# Hauptplatine.net
KiCad netlist of a schematic drawn in EAGLE
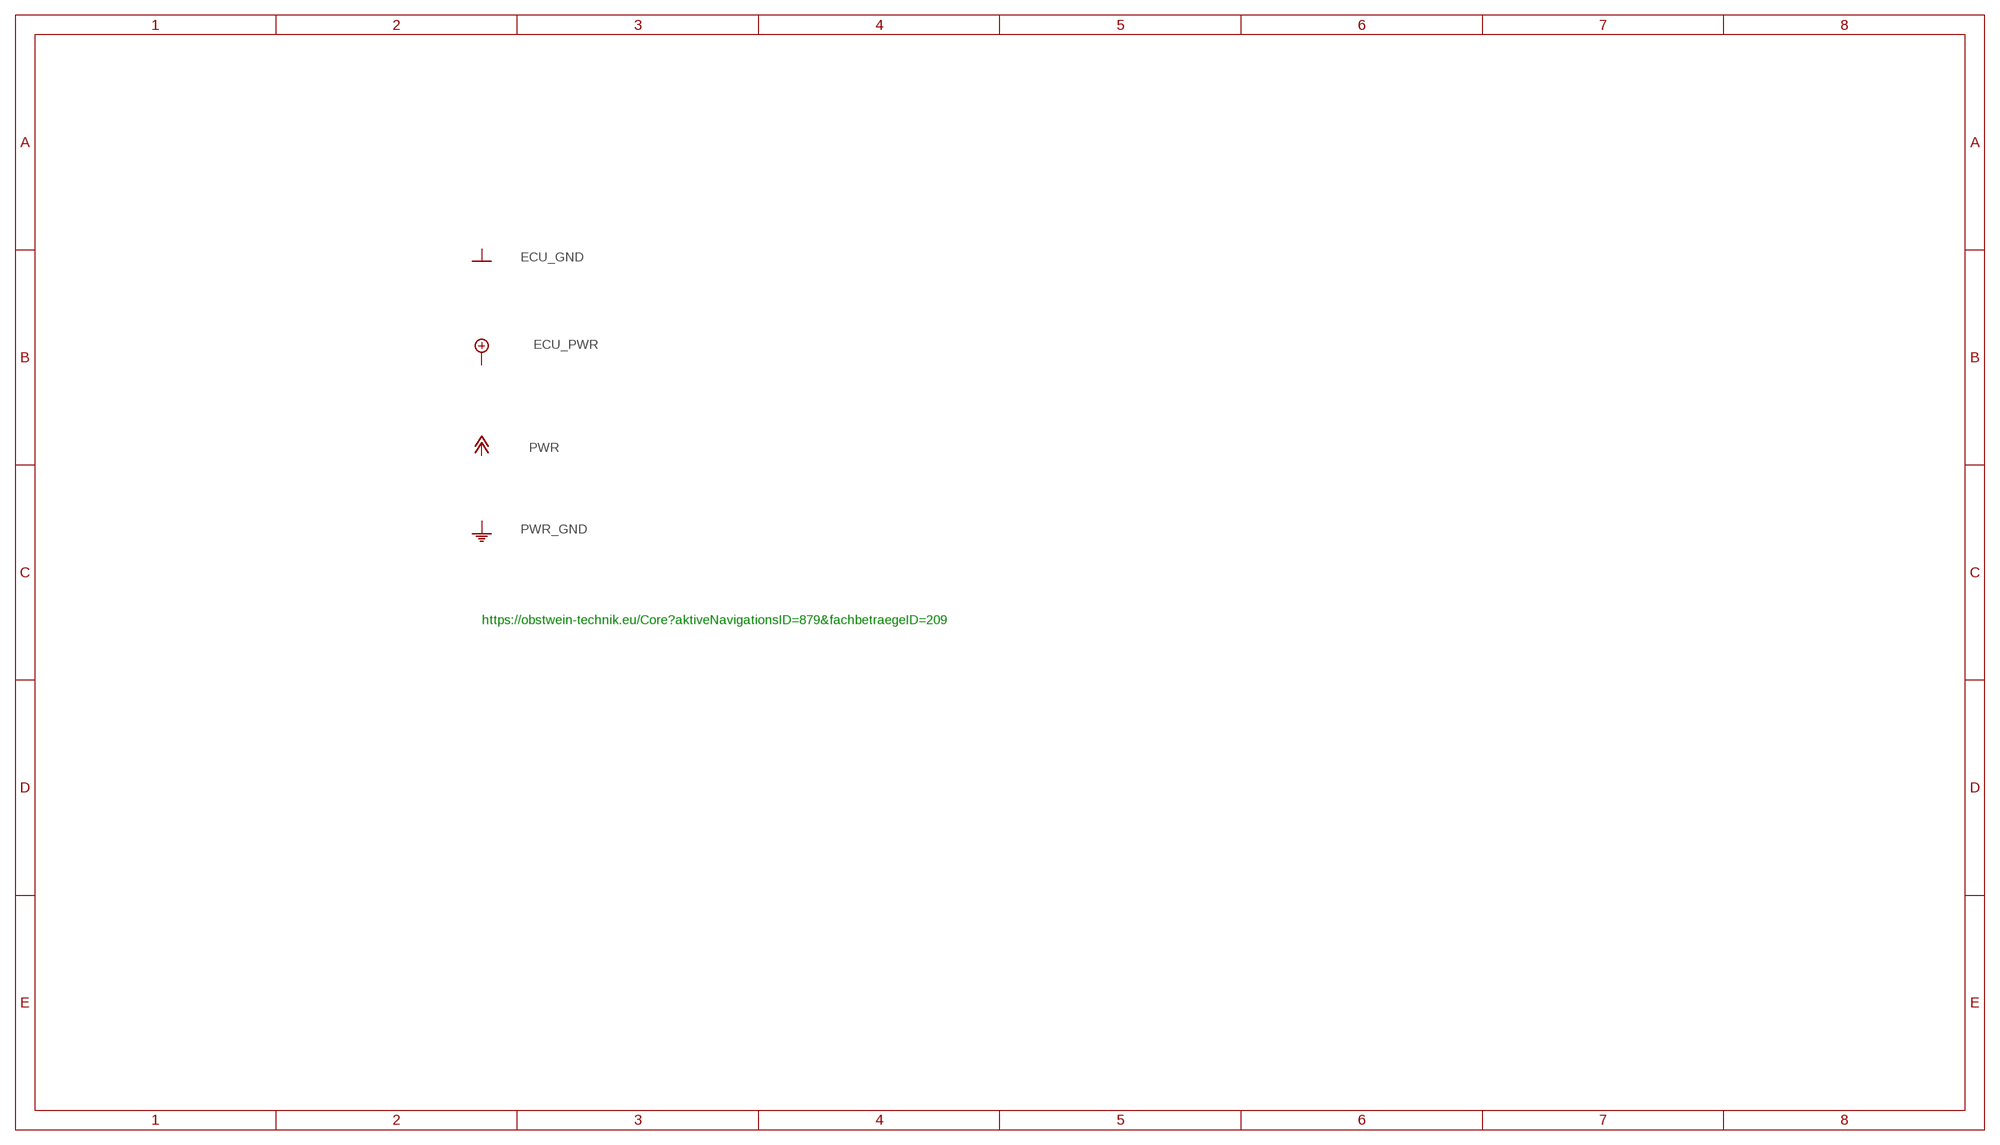
[diagram p0: schematic, sheet 1]
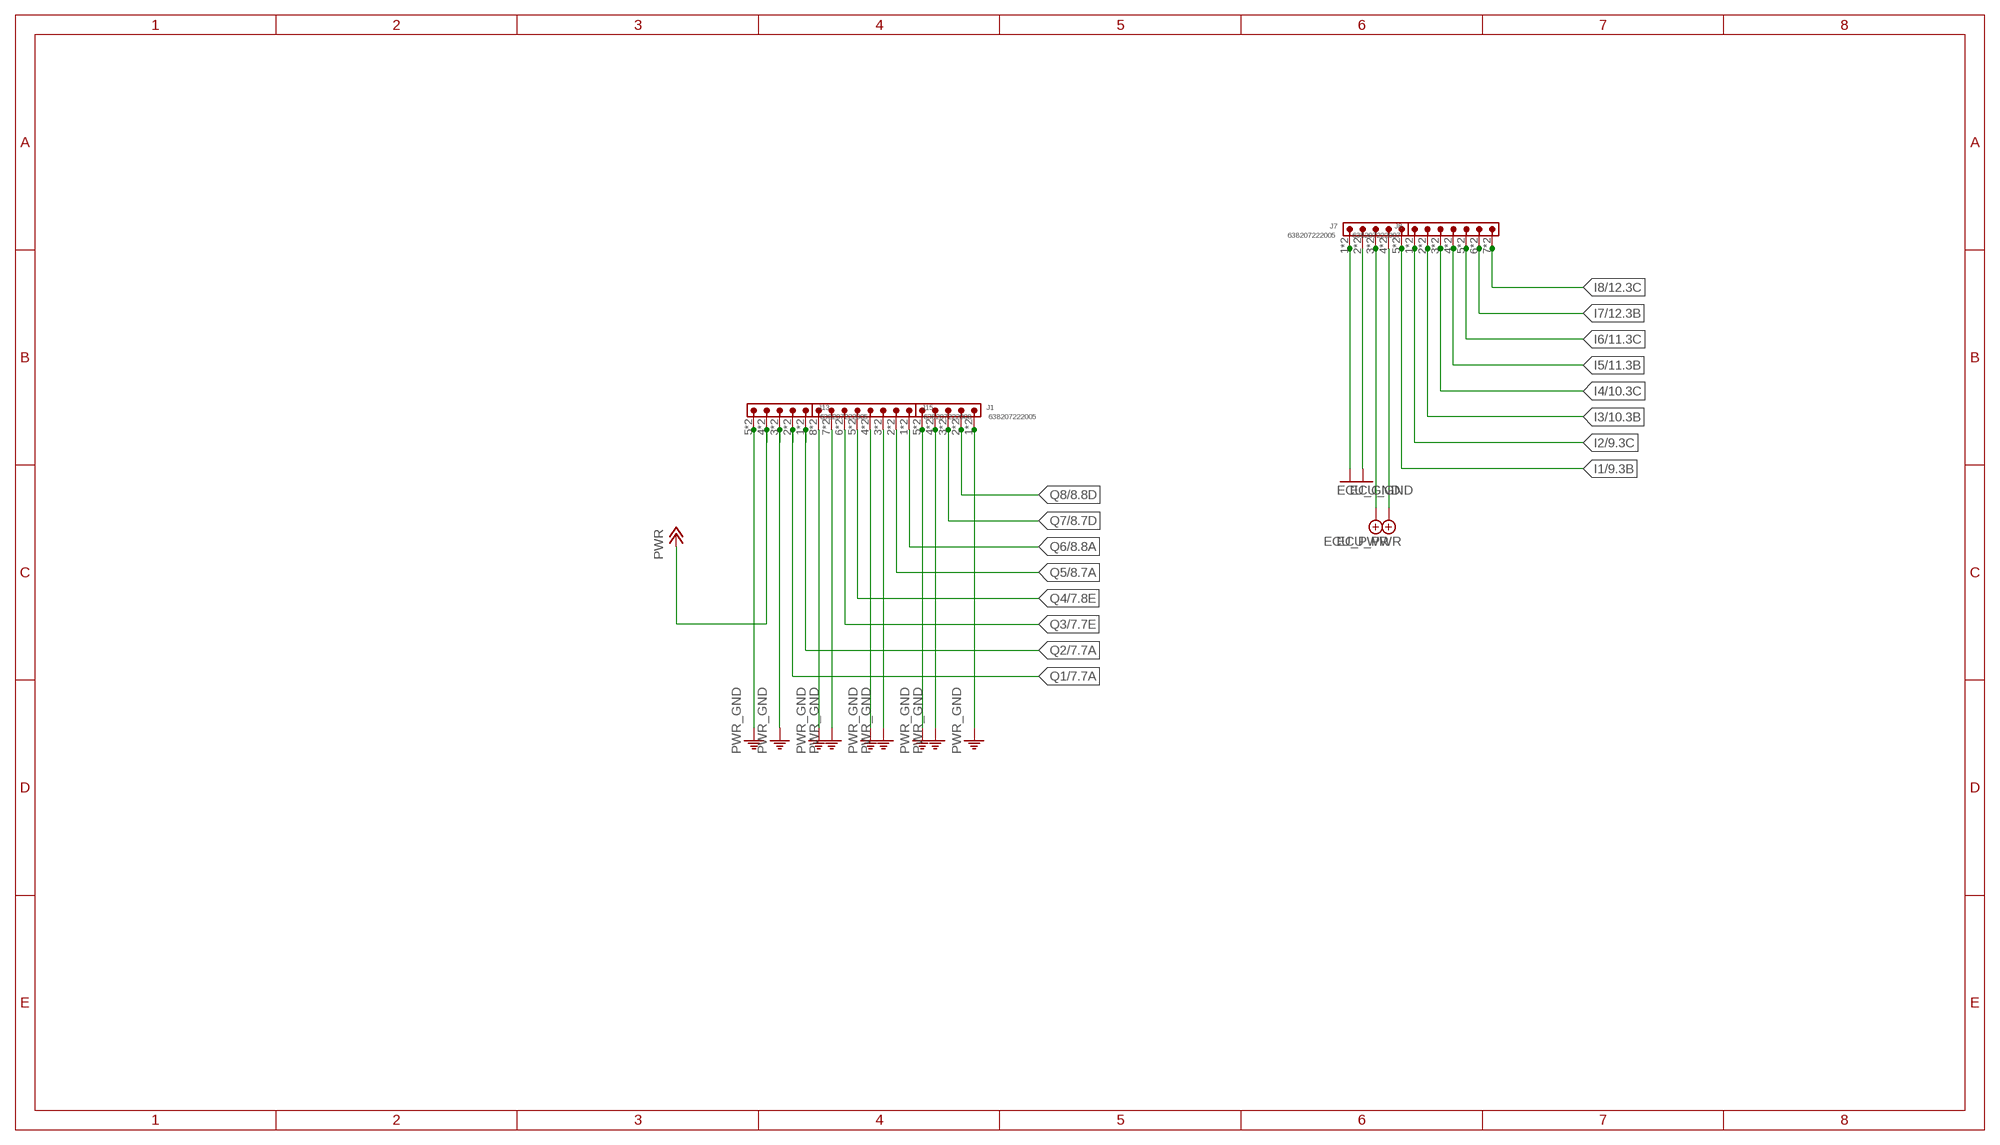
[diagram p1: schematic, sheet 2]
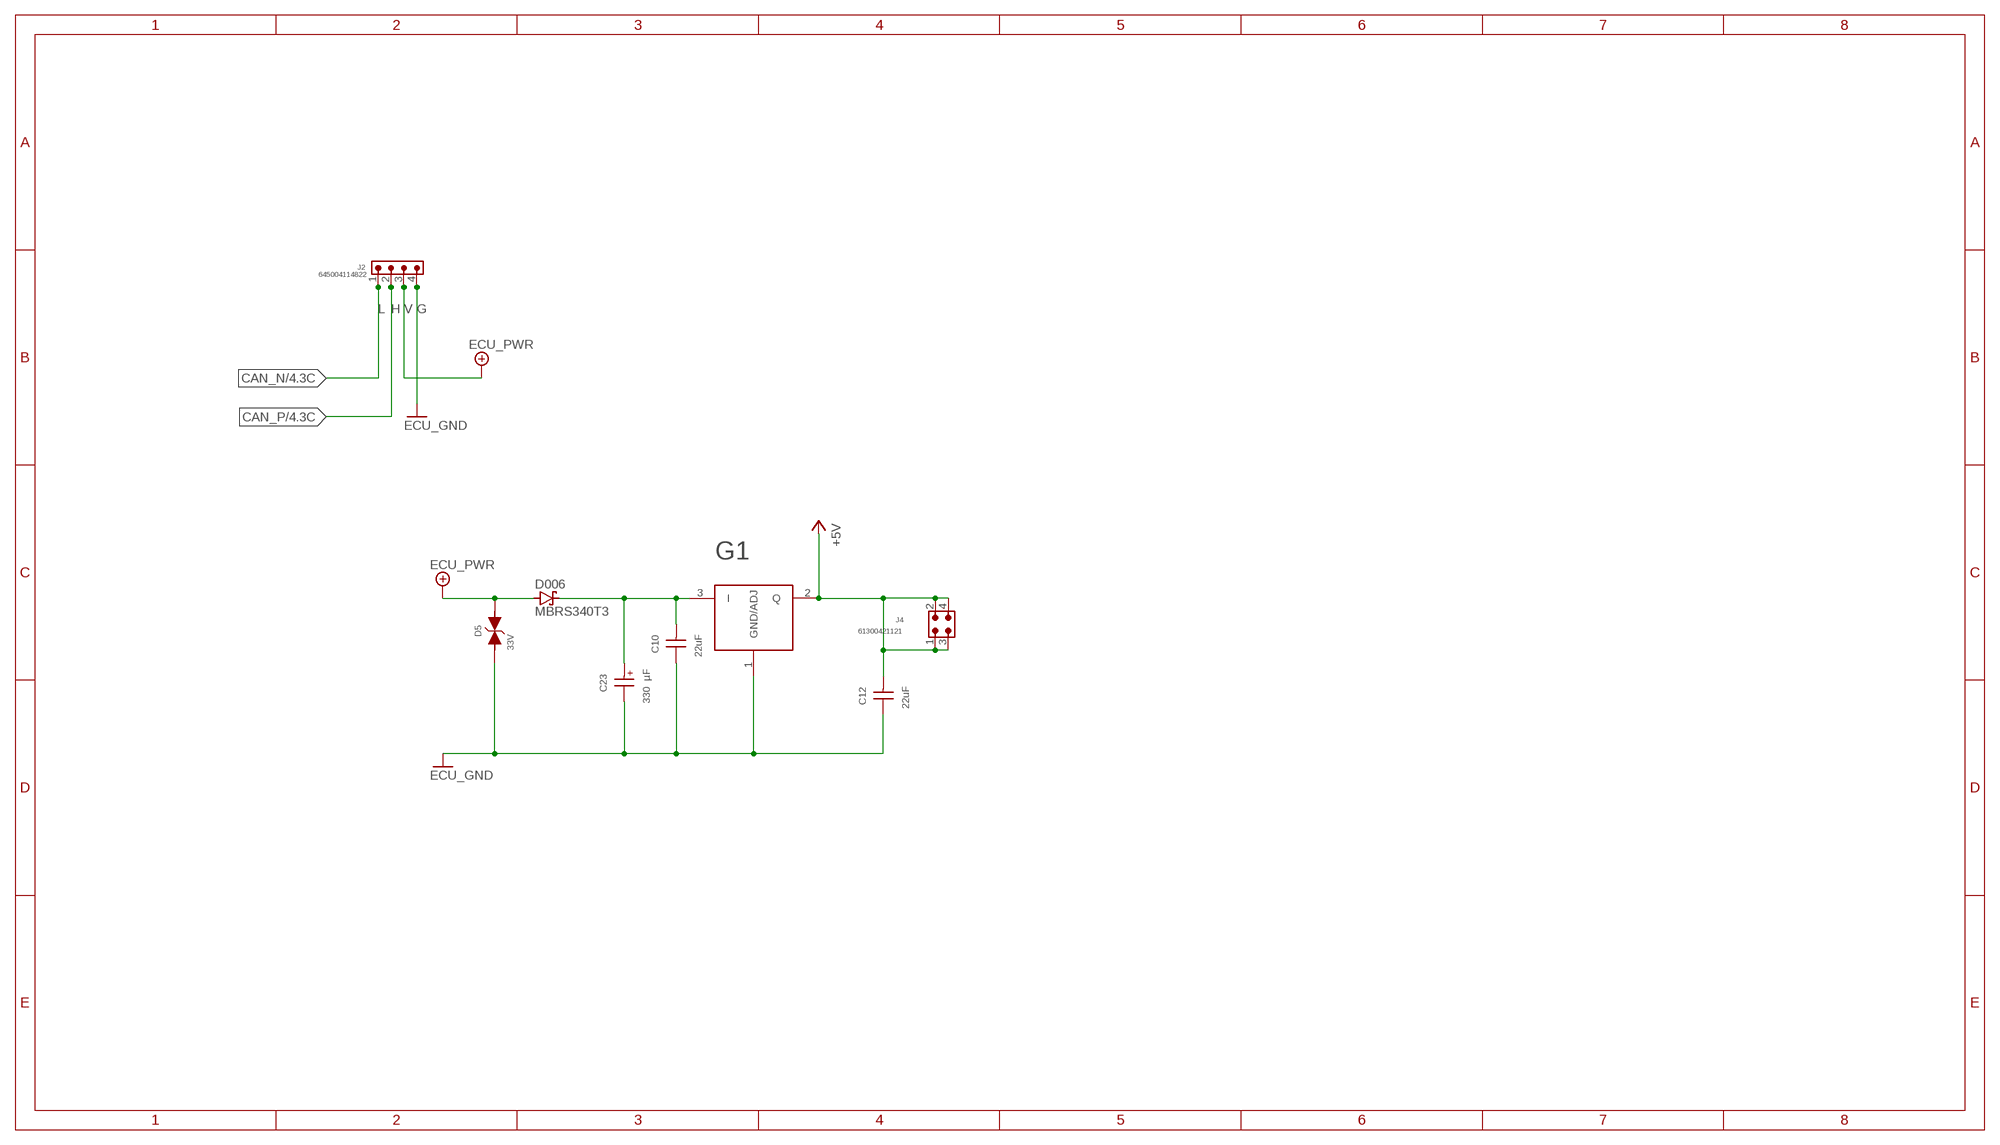
[diagram p2: schematic, sheet 3]
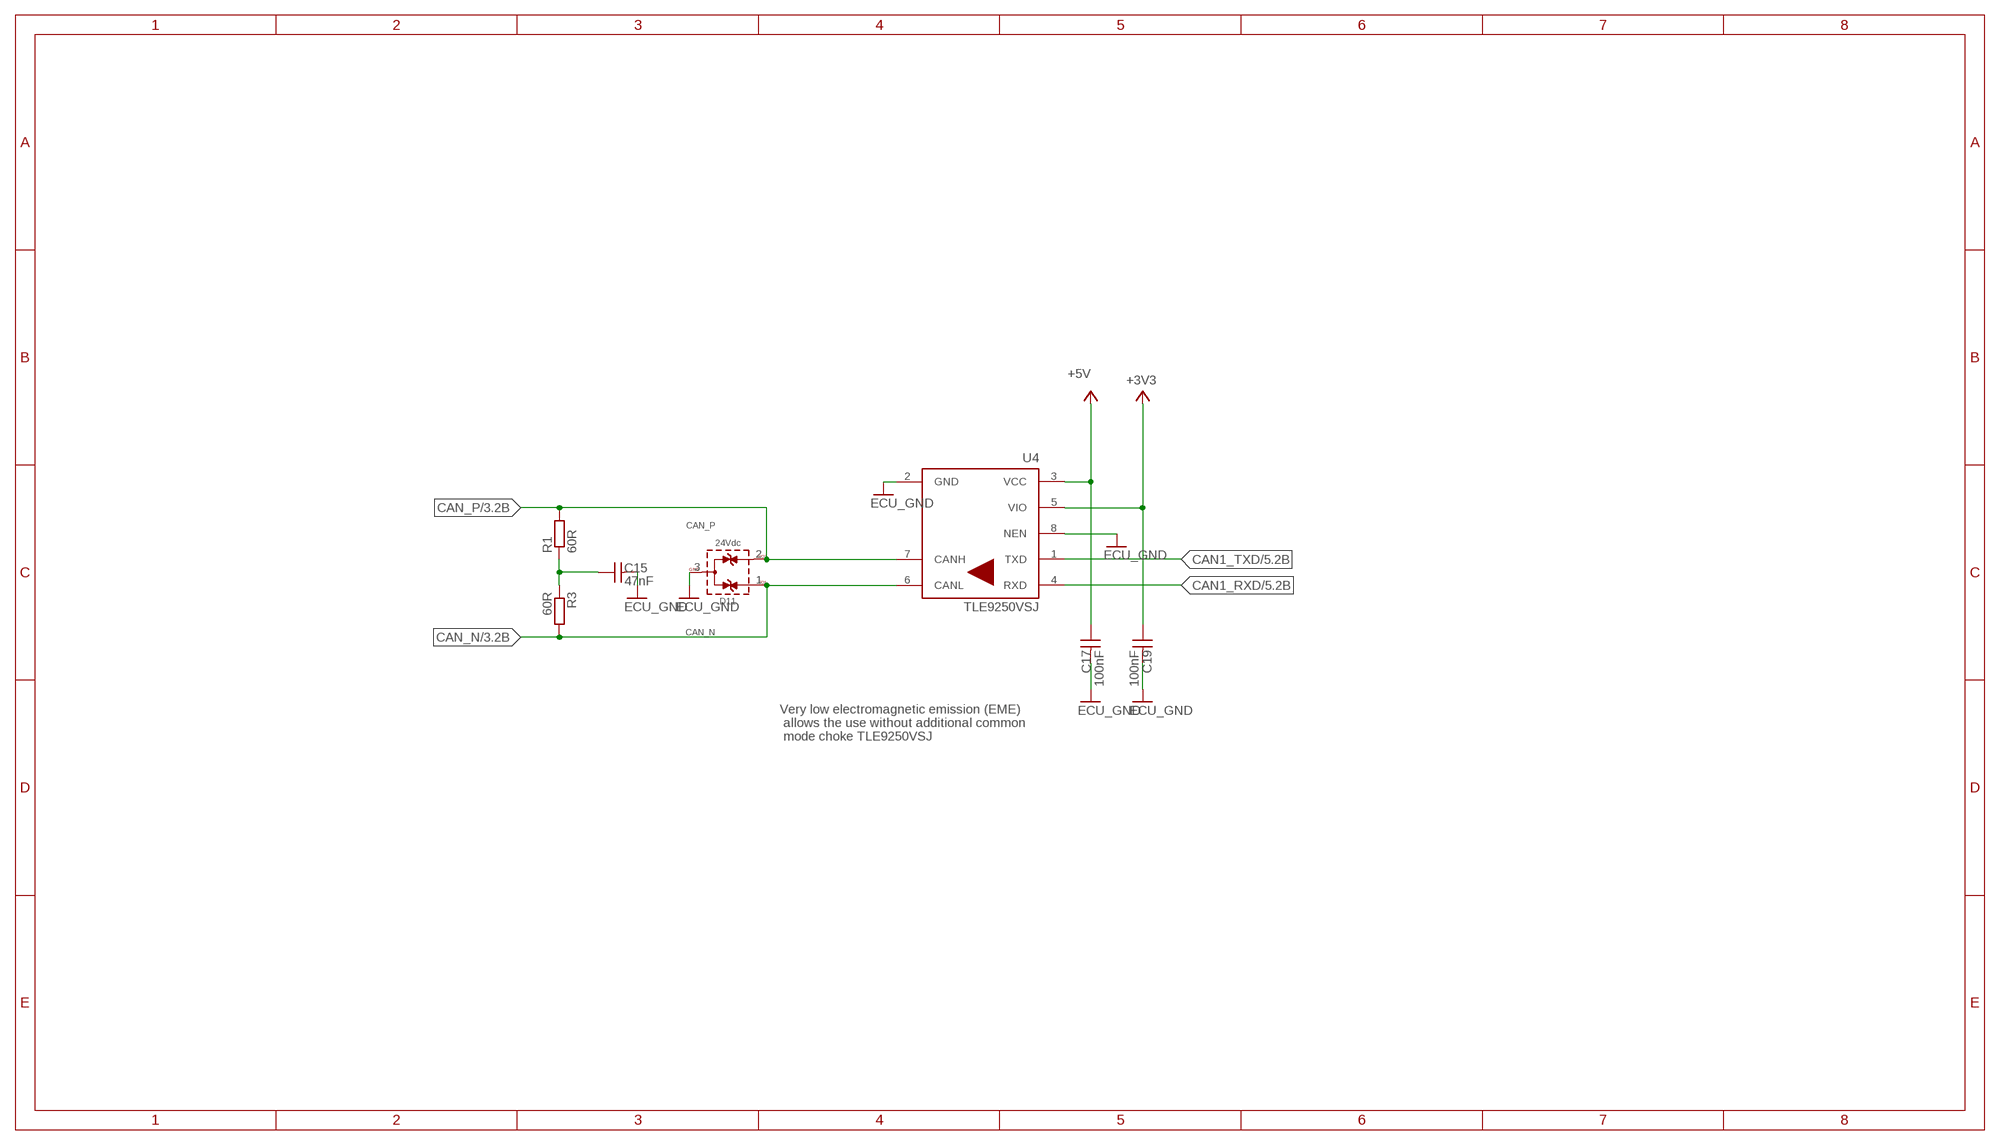
[diagram p3: schematic, sheet 4]
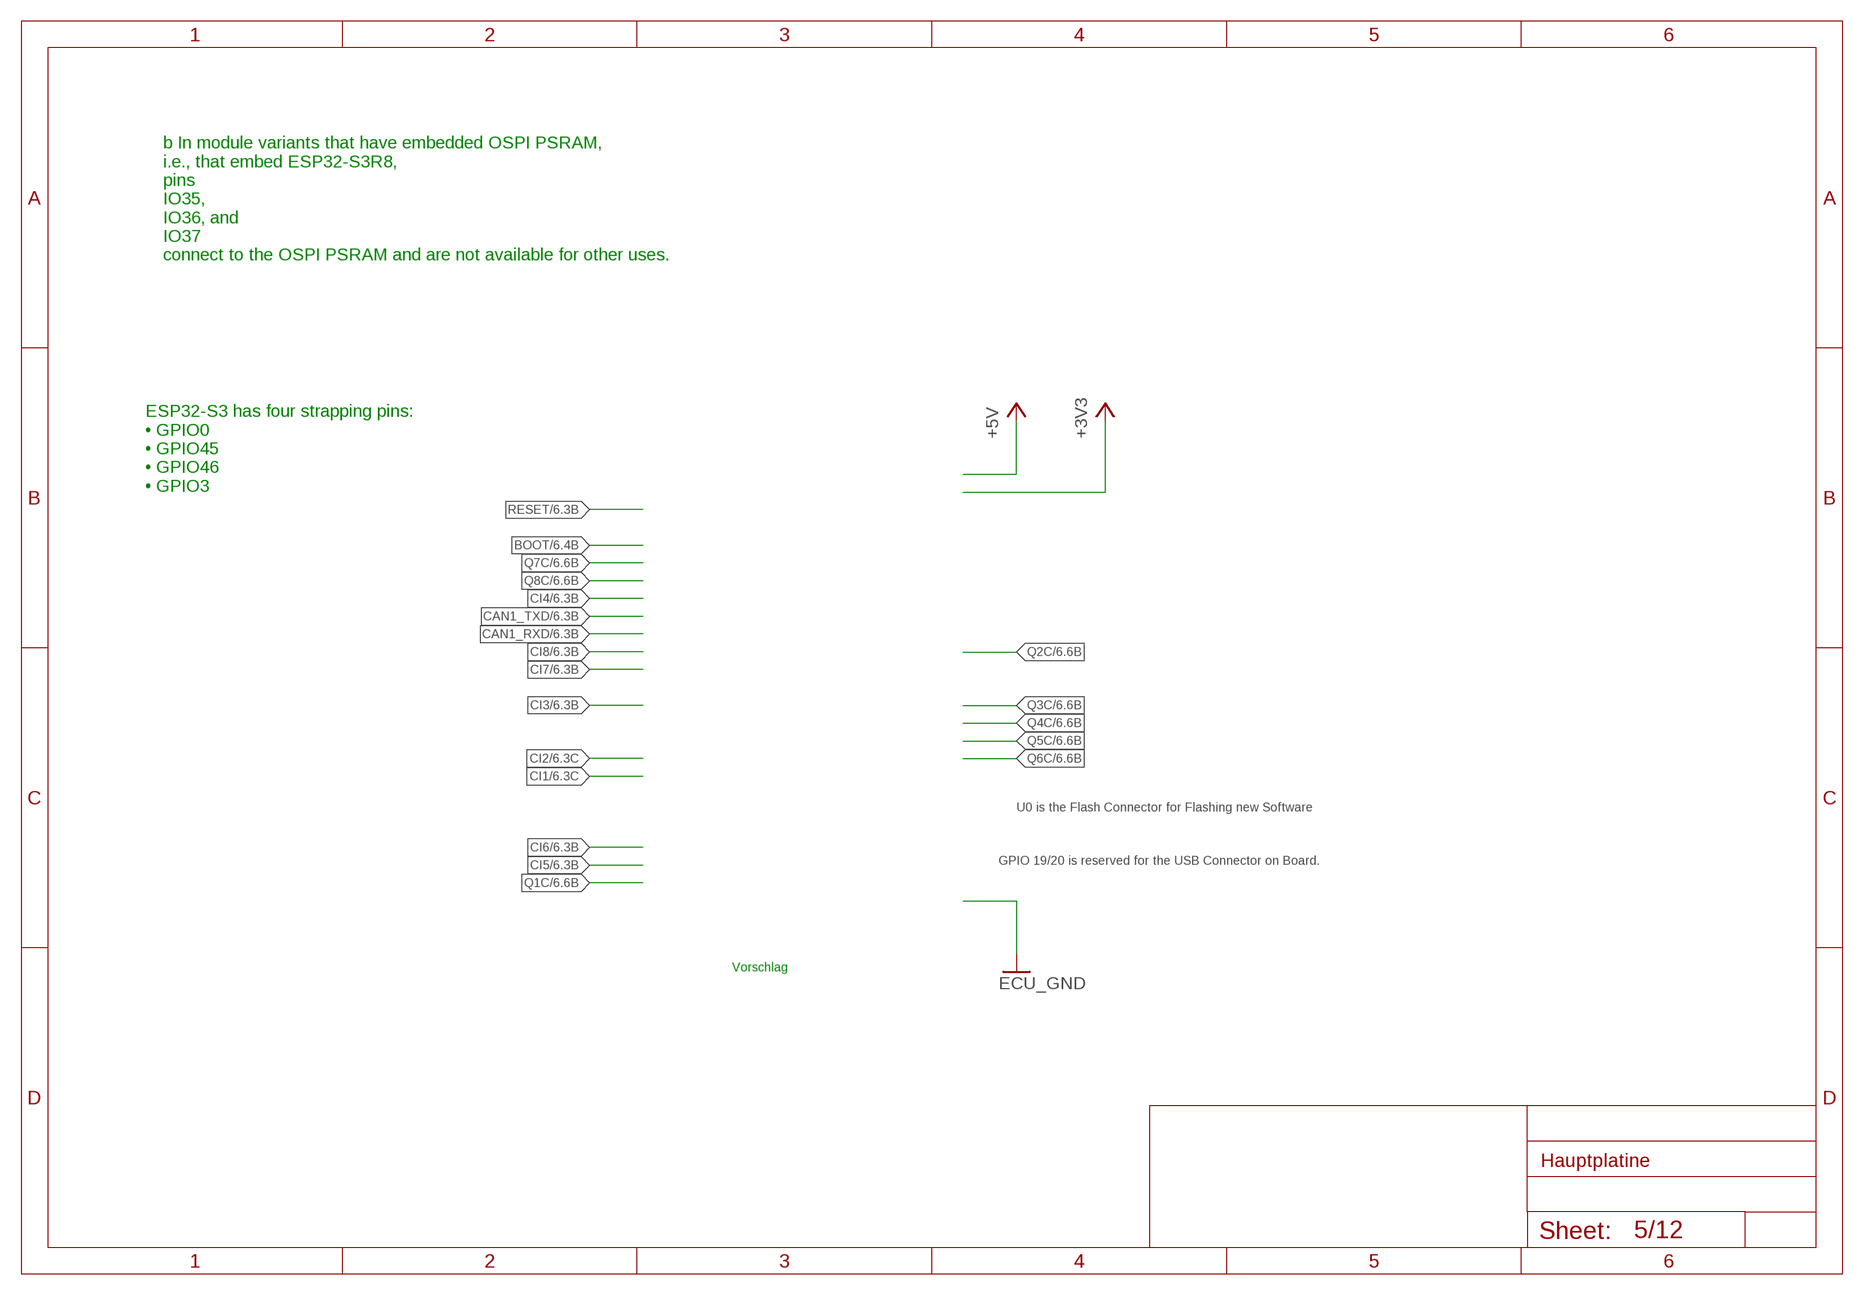
[diagram p4: schematic, sheet 5]
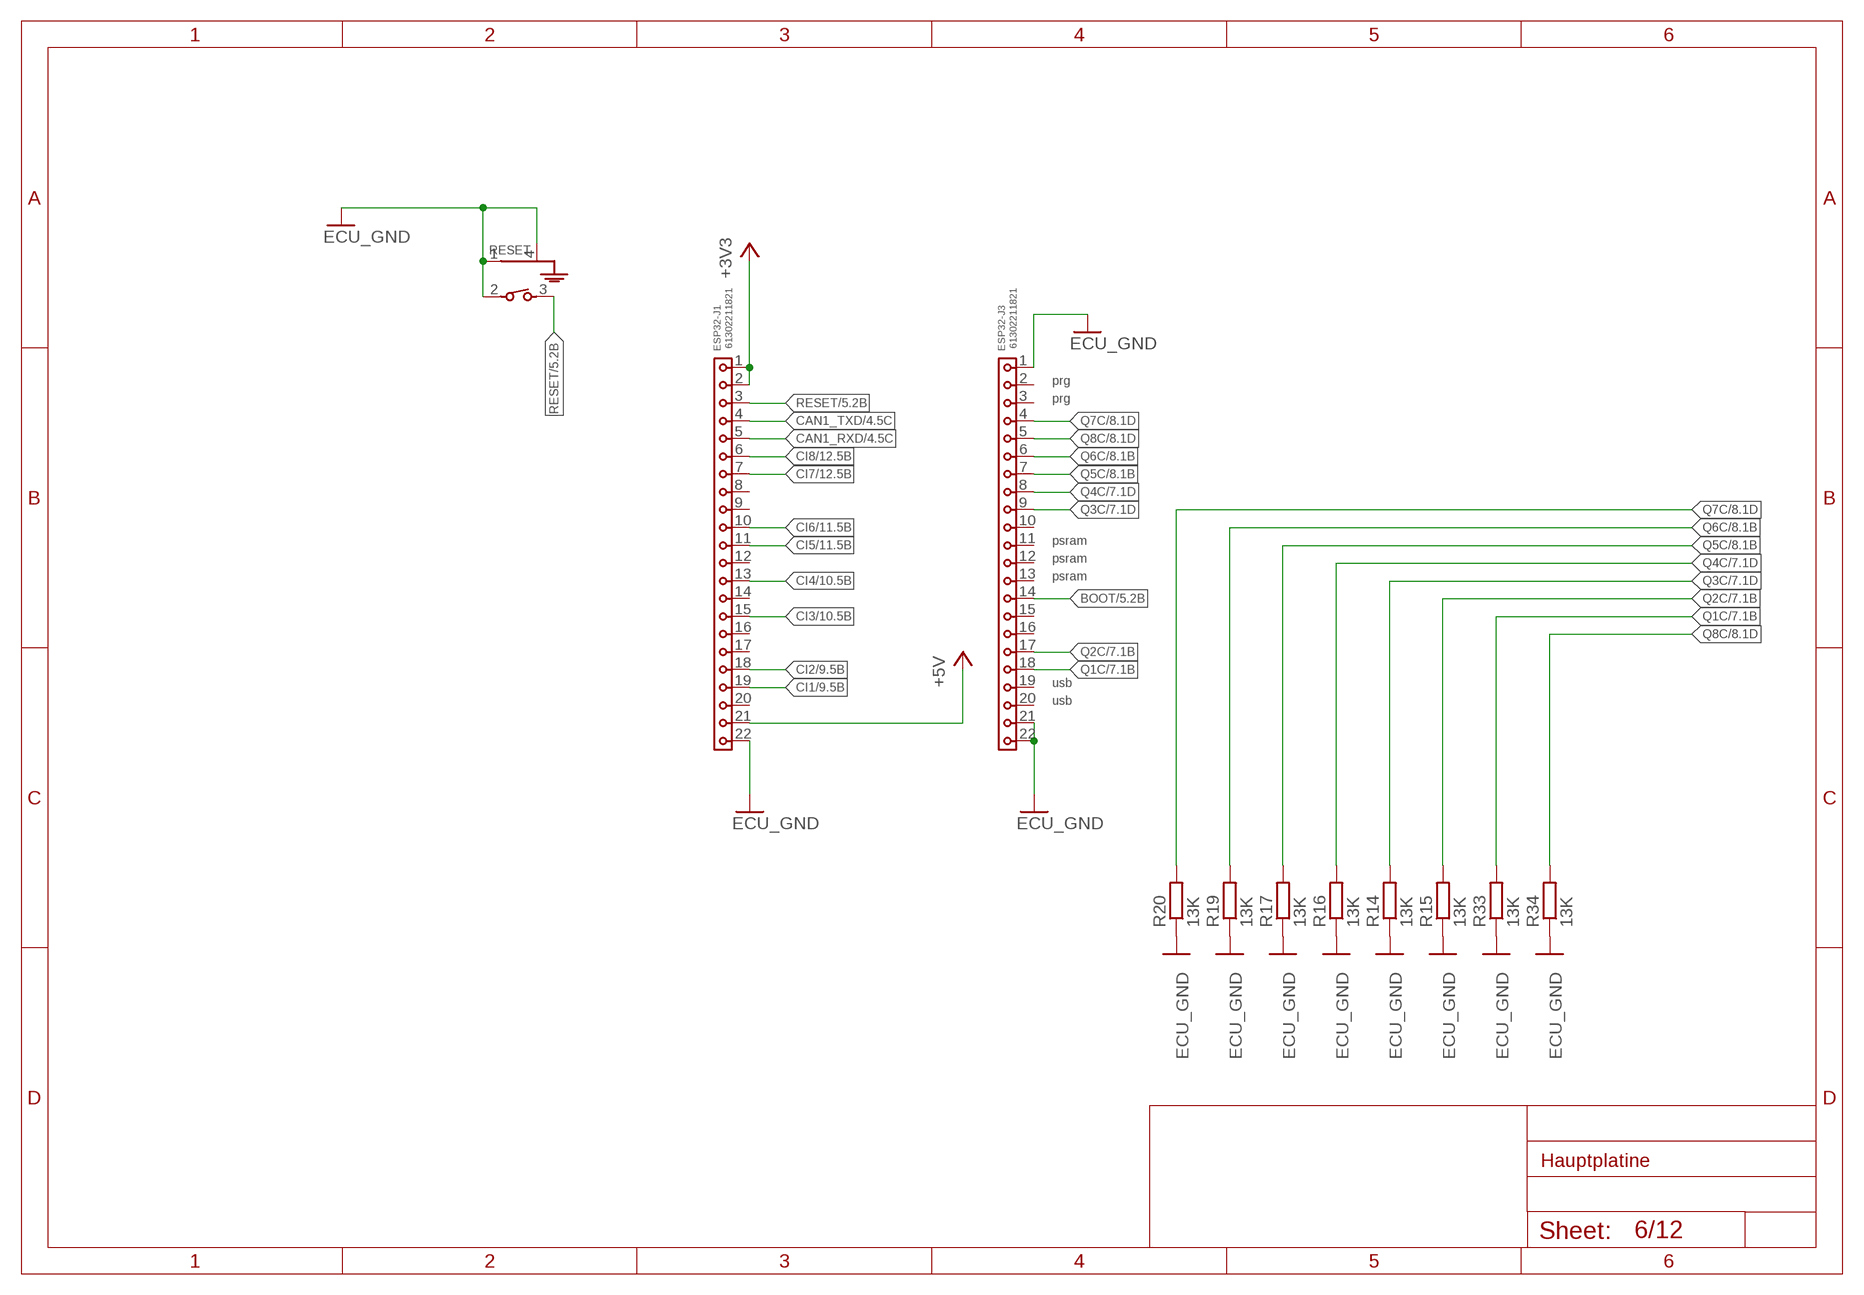
[diagram p5: schematic, sheet 6]
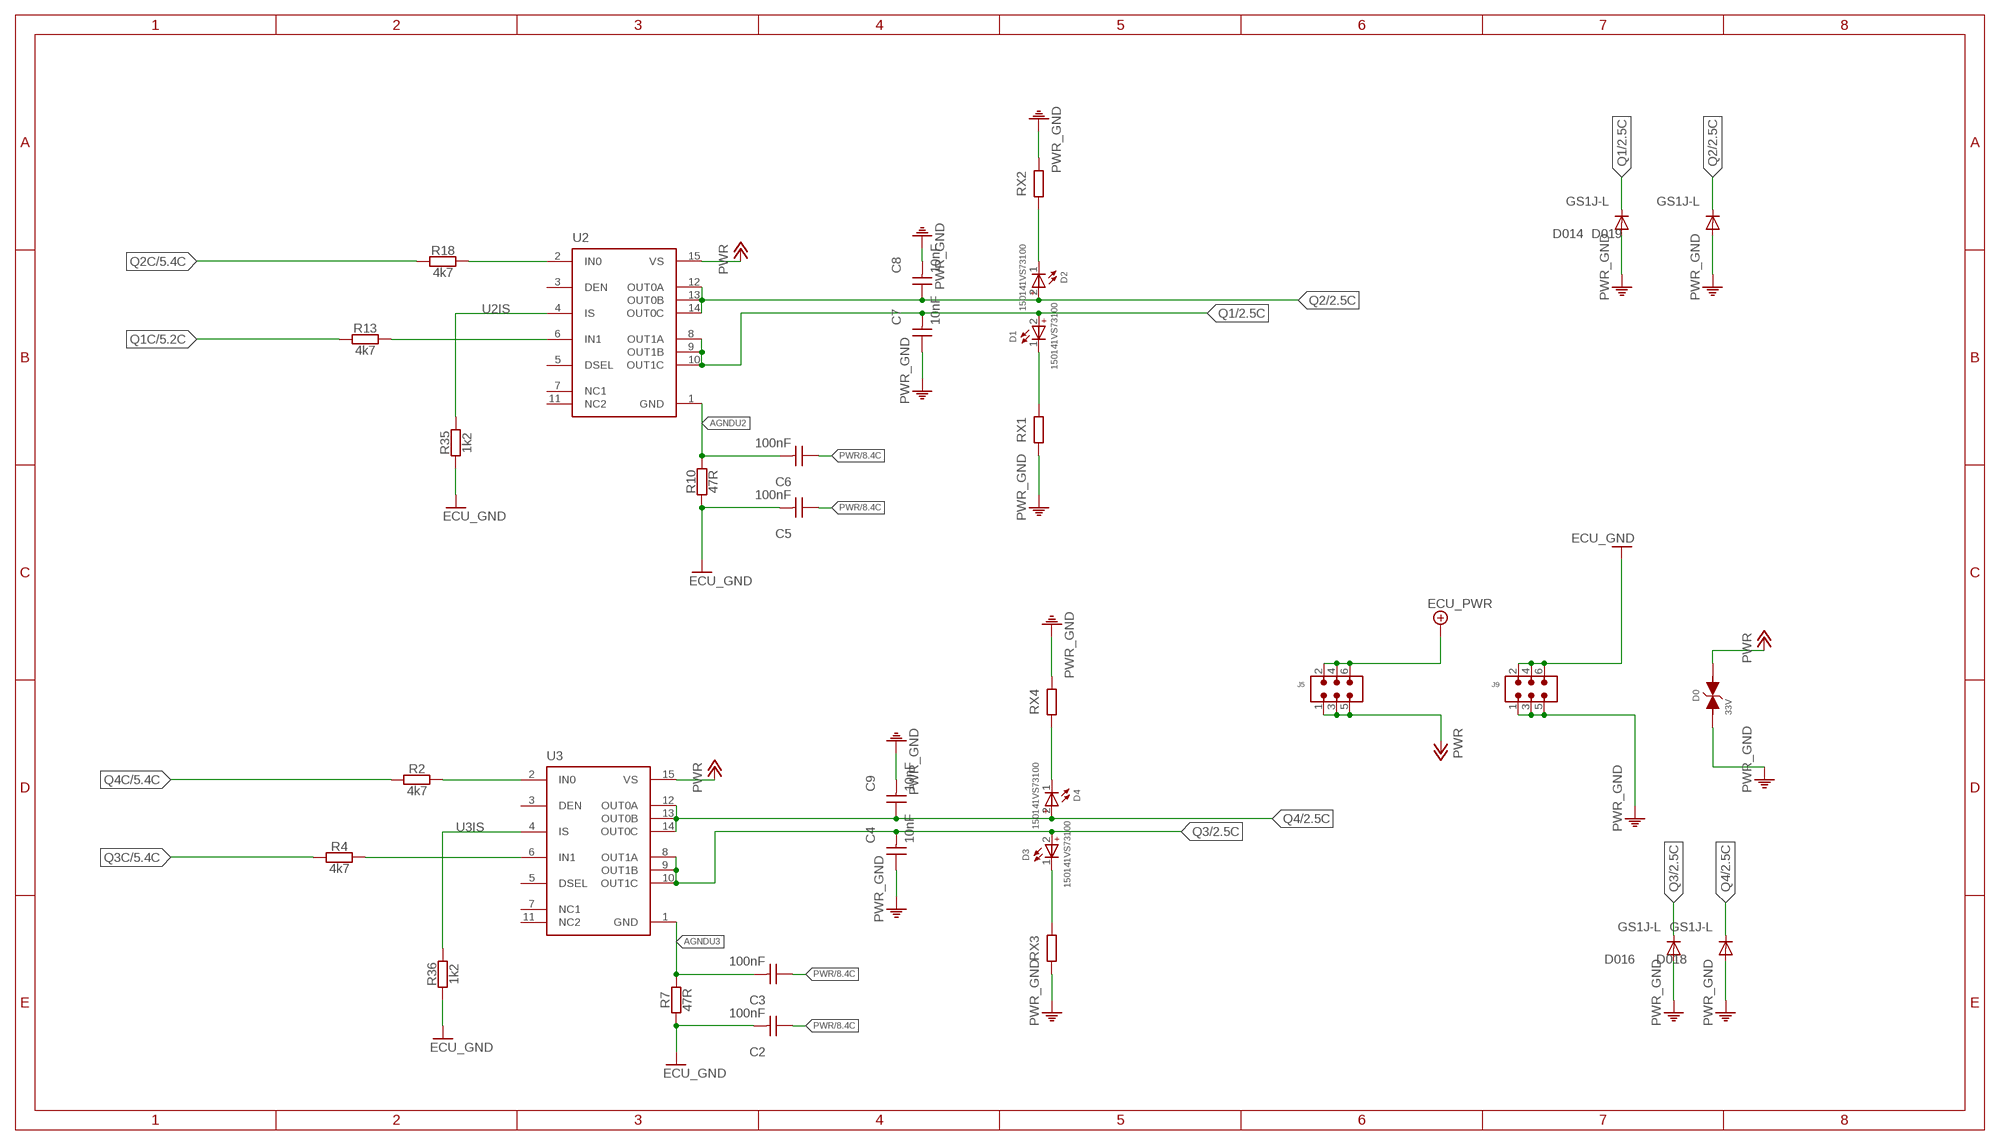
[diagram p6: schematic, sheet 7]
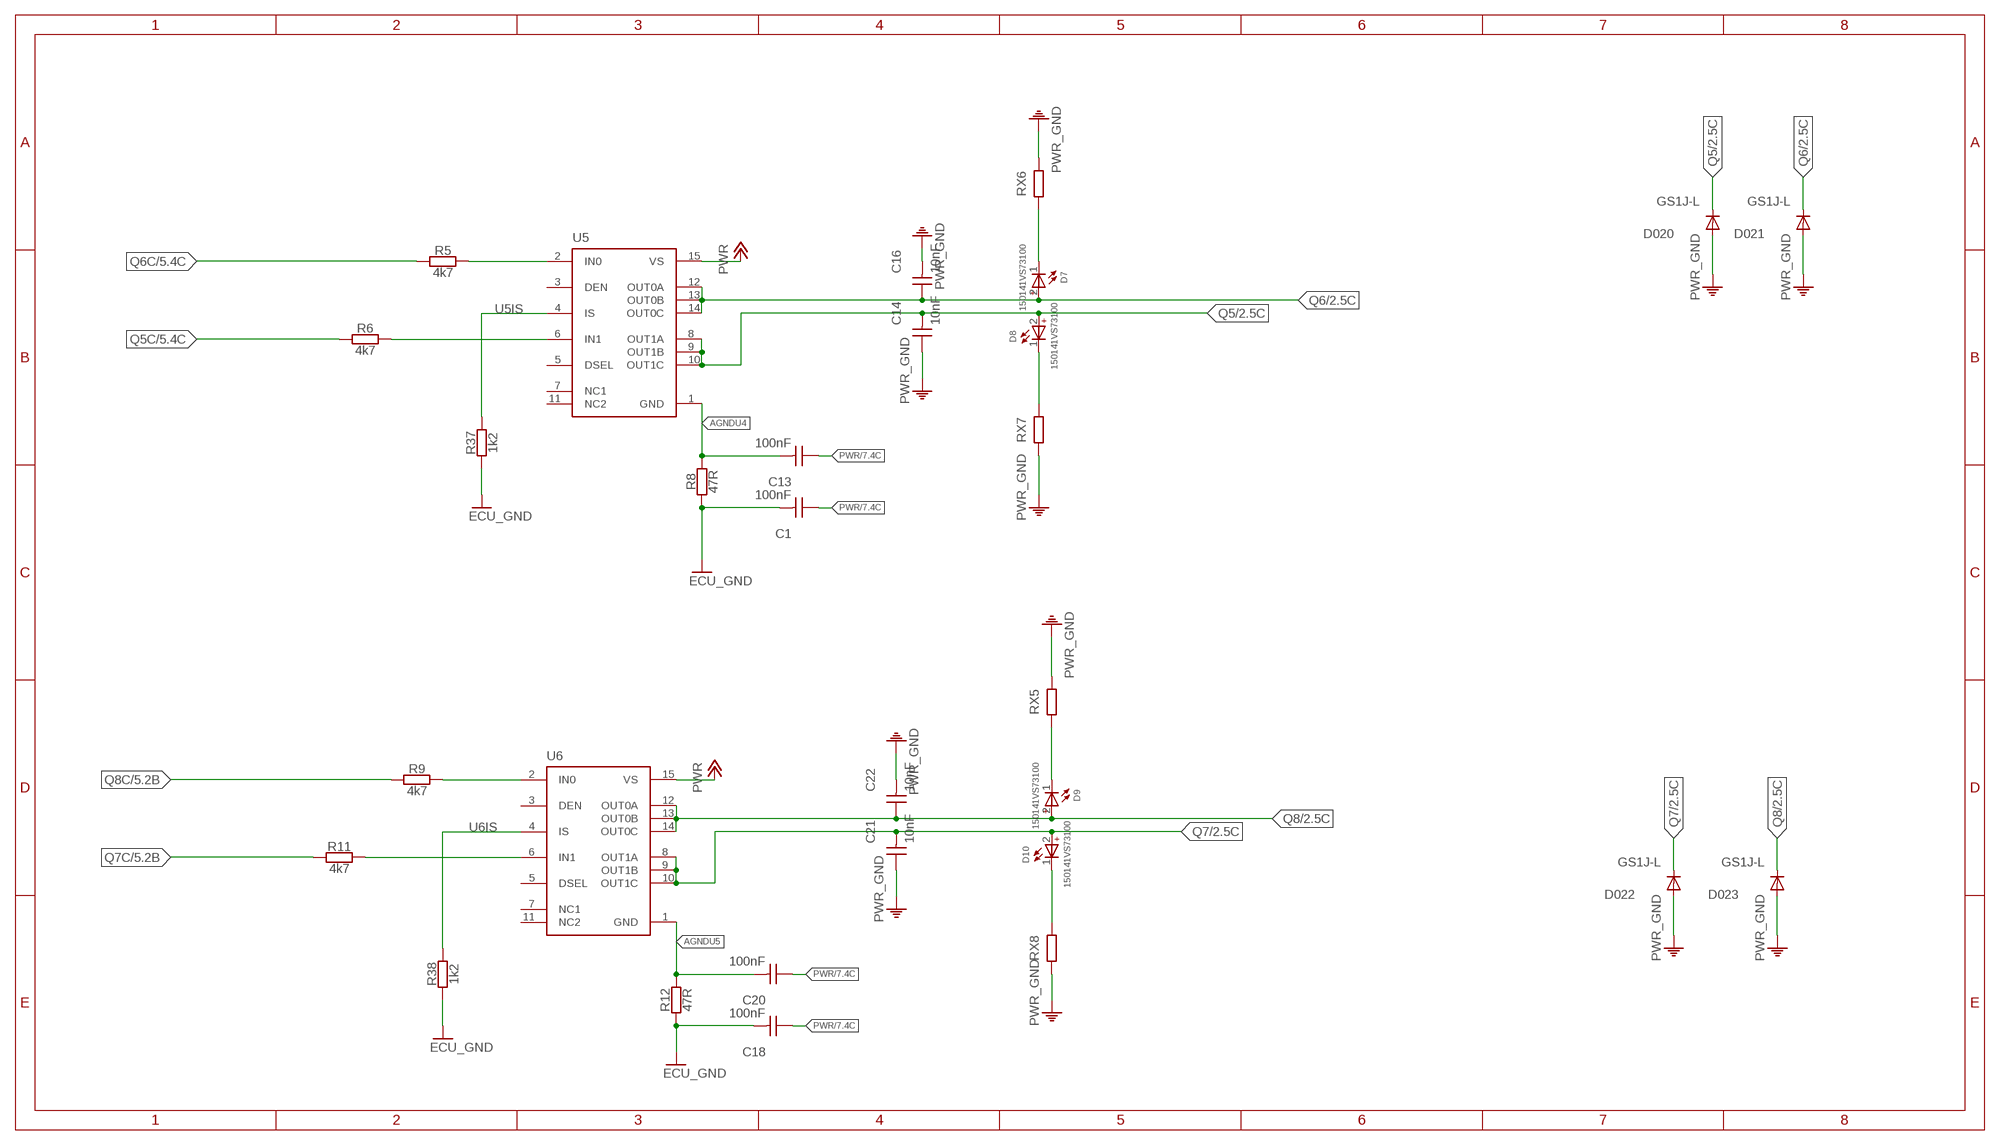
[diagram p7: schematic, sheet 8]
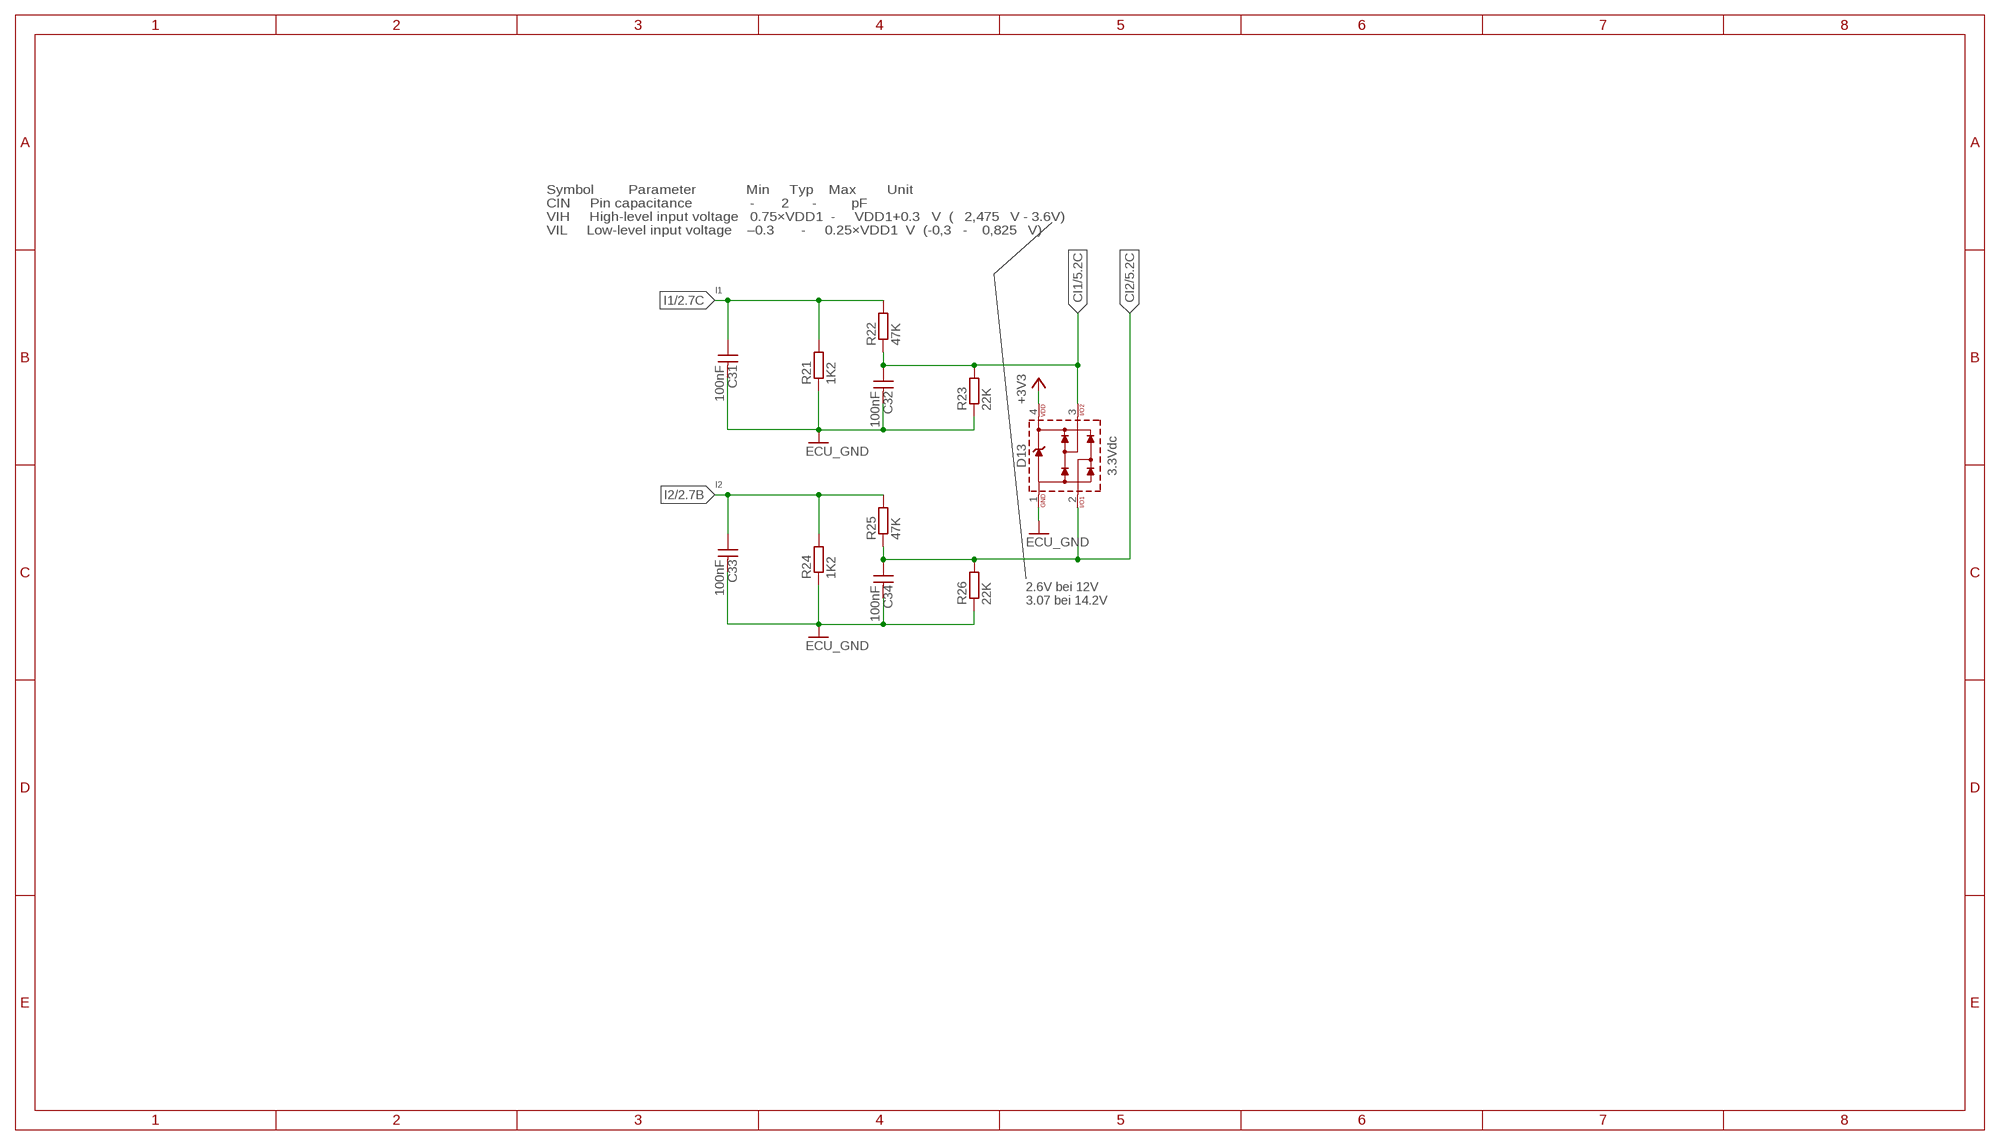
[diagram p8: schematic, sheet 9]
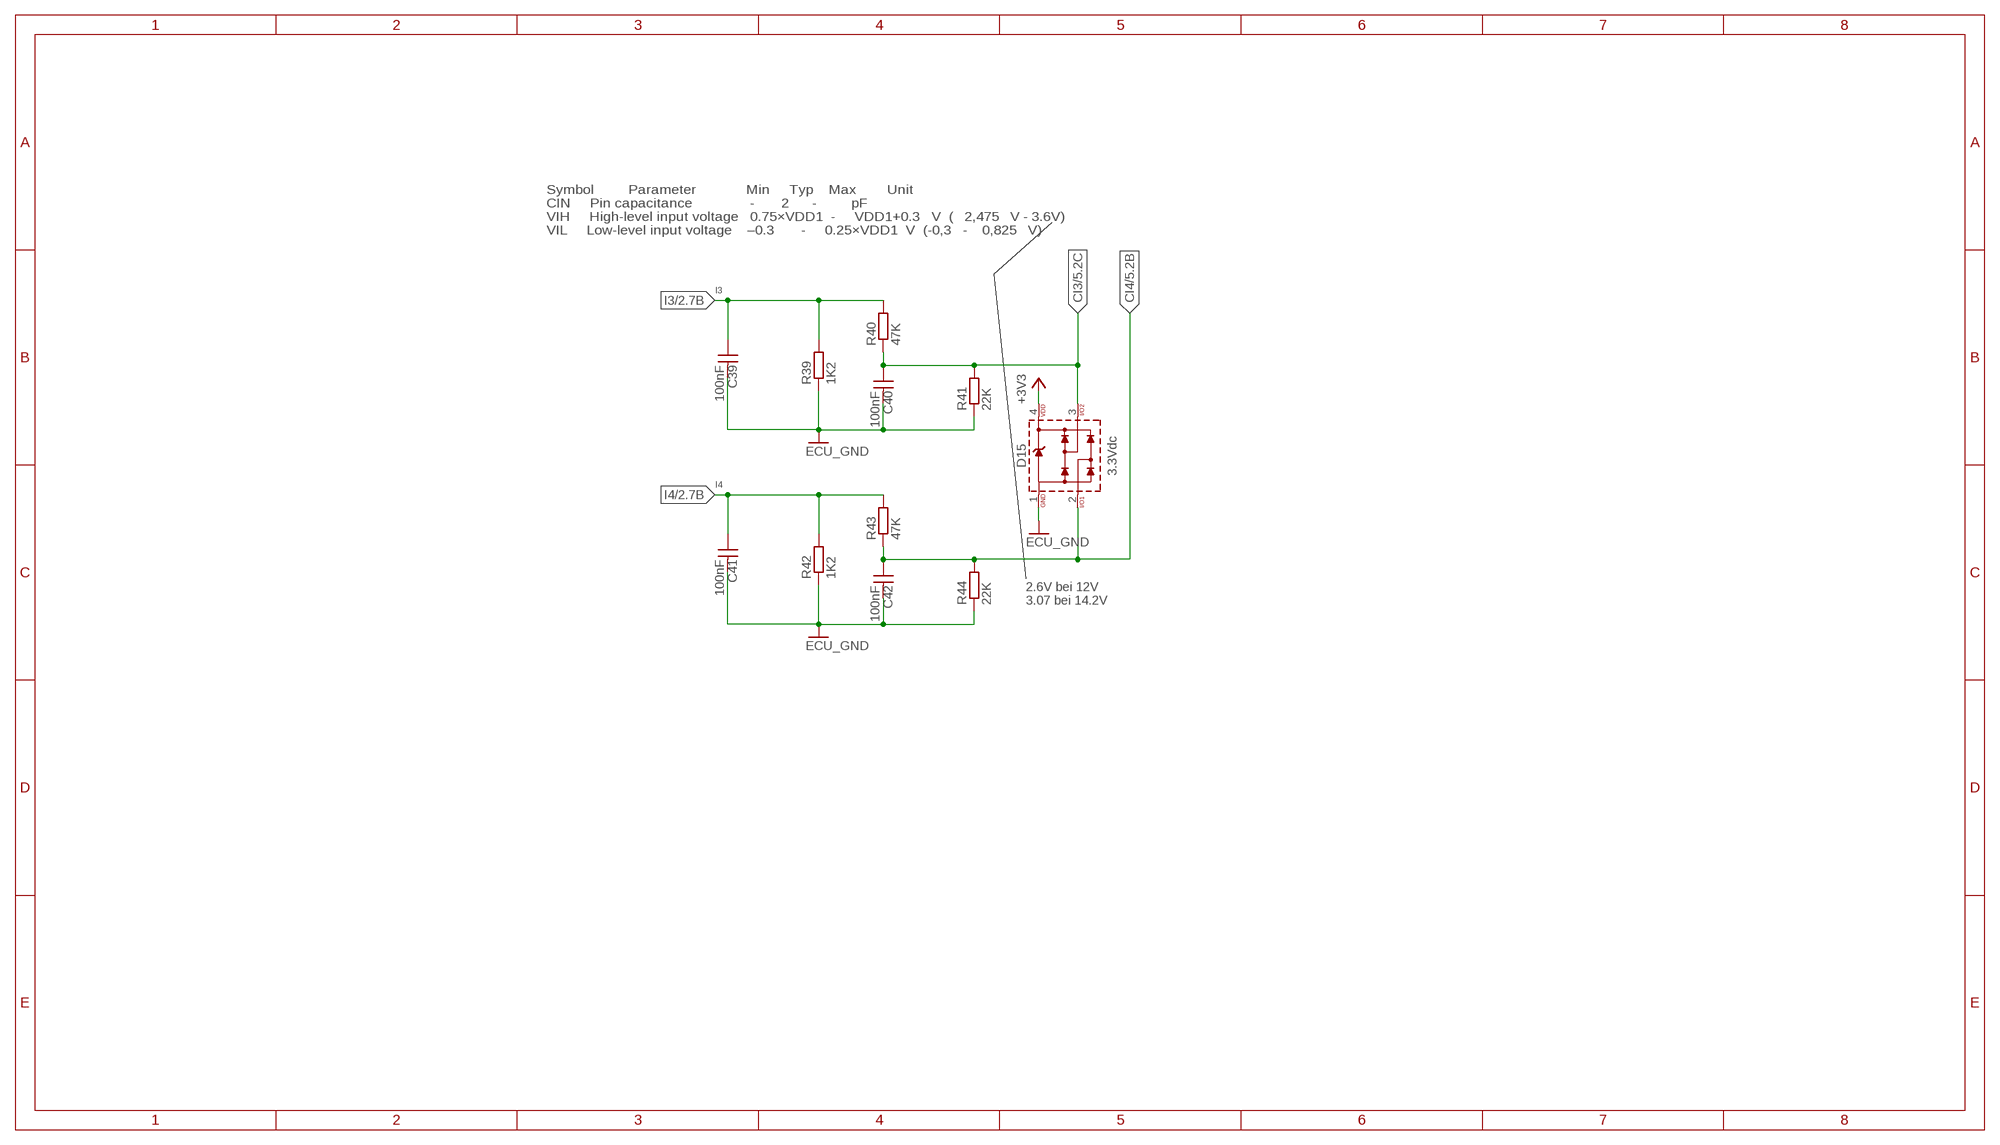
[diagram p9: schematic, sheet 10]
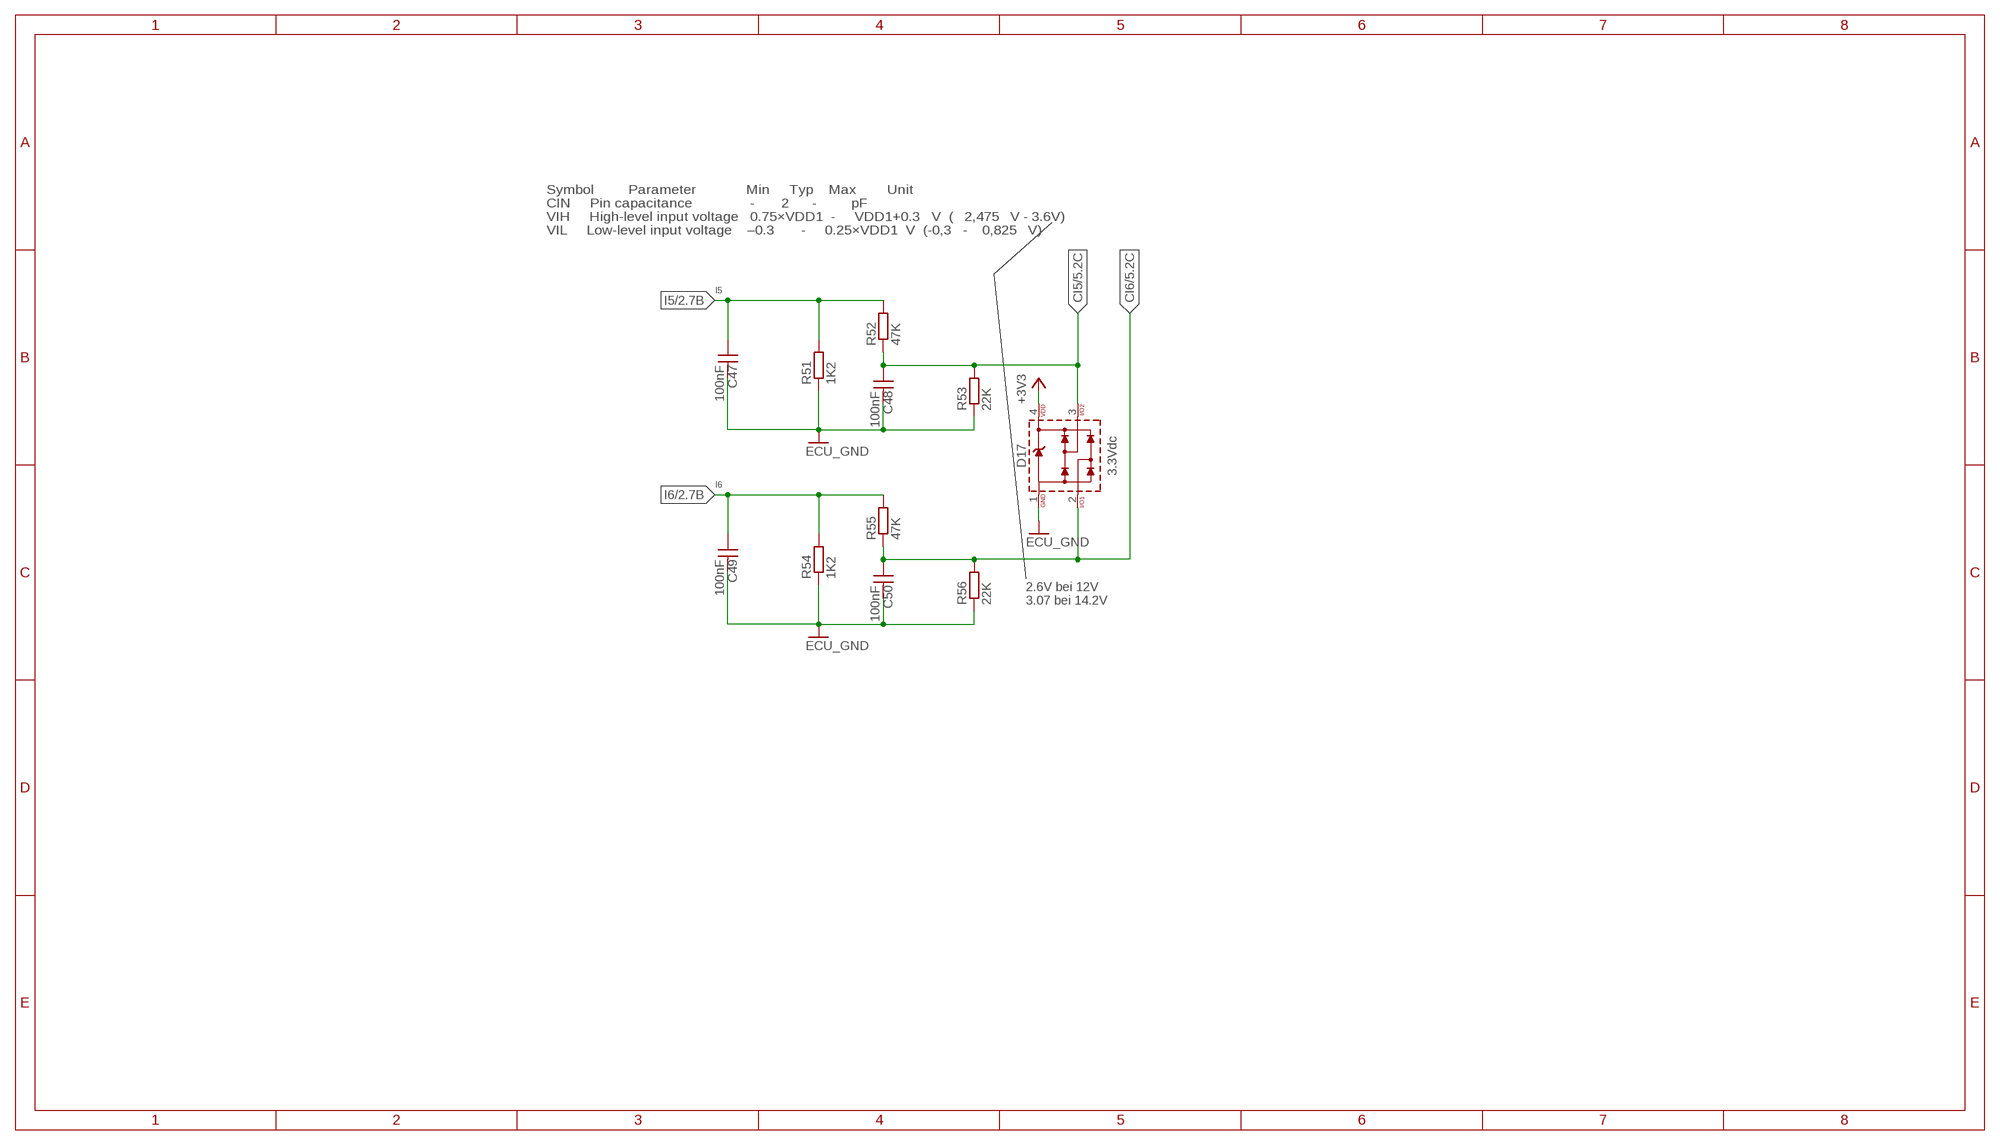
[diagram p10: schematic, sheet 11]
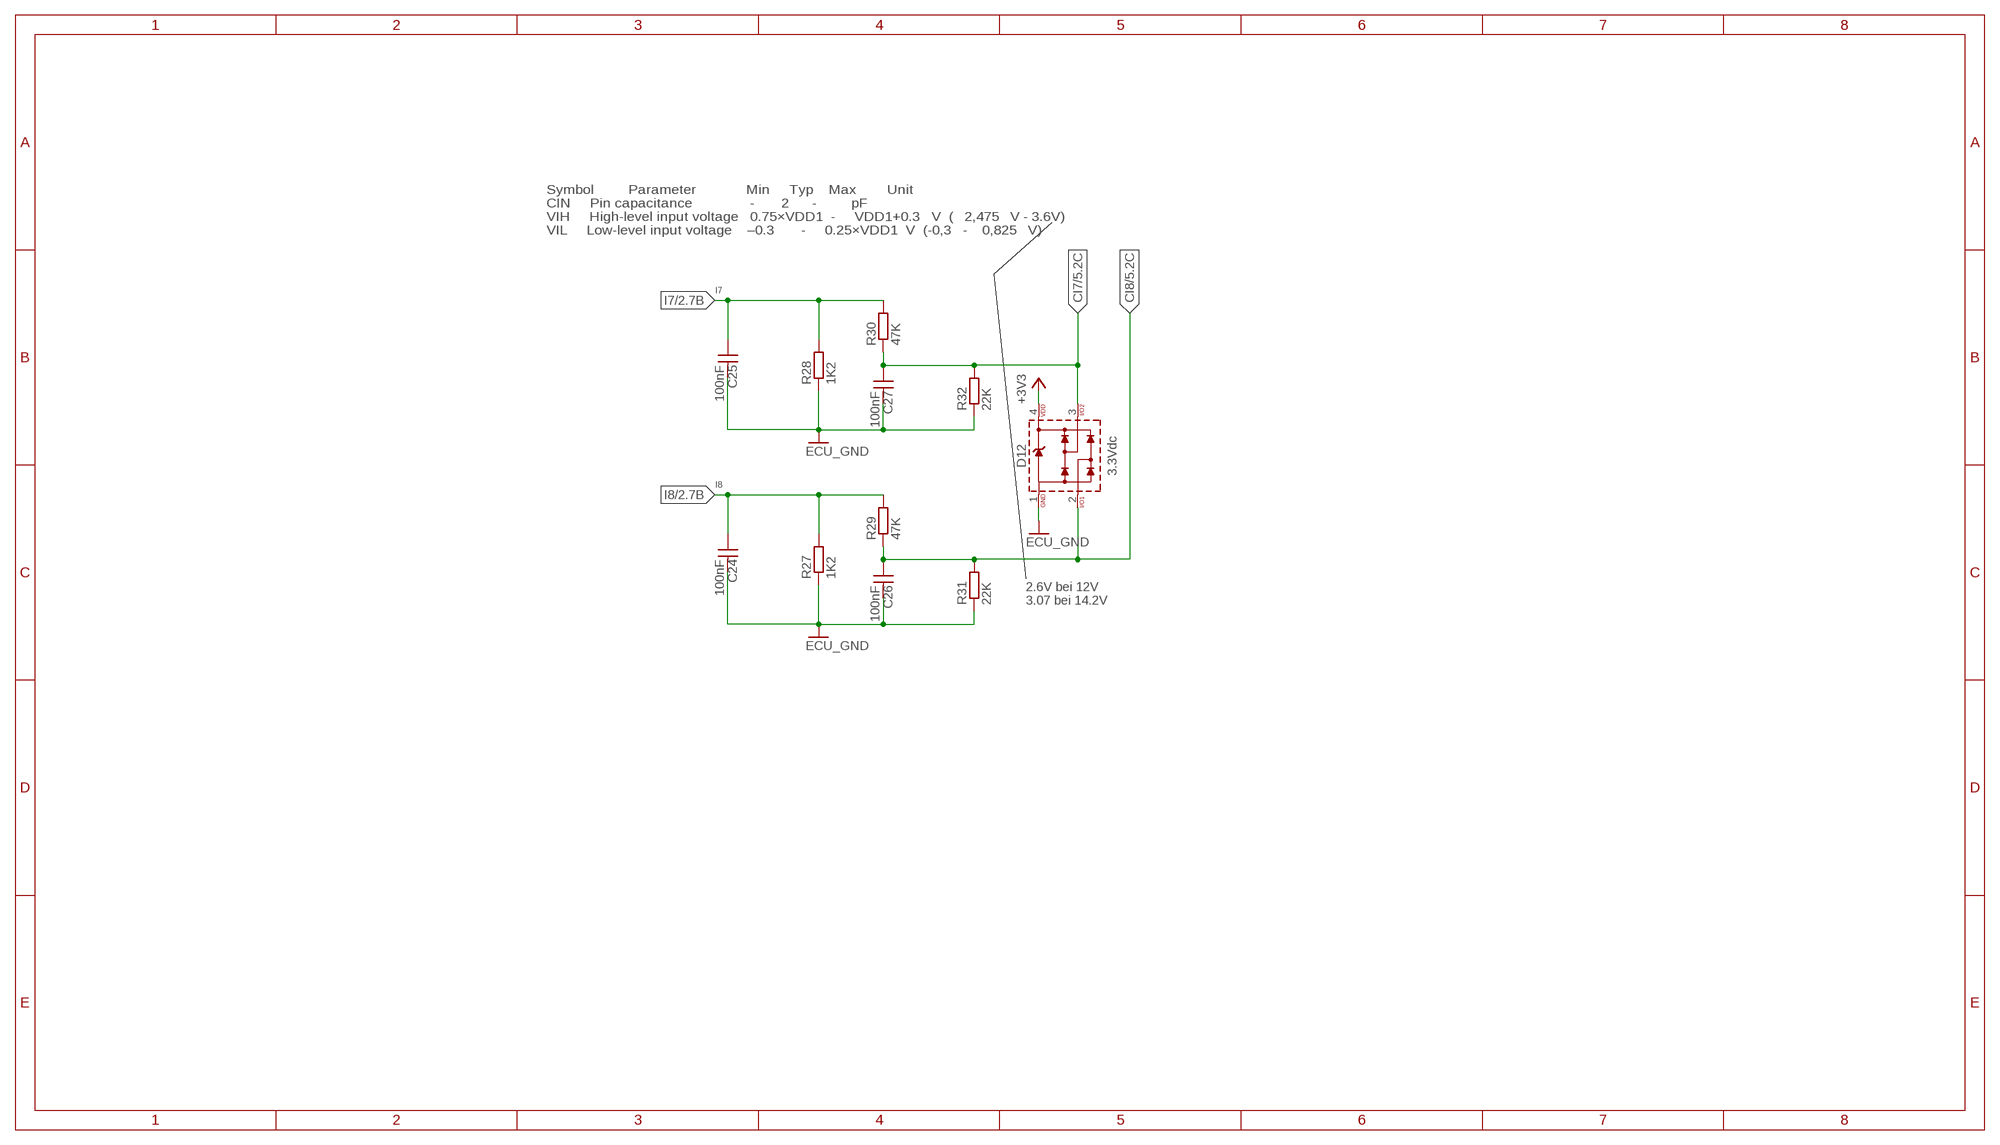
[diagram p11: schematic, sheet 12]

(export (version "E")
  (design (tool "Eeschema 10.0.6"))
  (components
    (comp (ref "C31")
      (value "100nF")
      (footprint "eagle-import:WCAP-CSGP_1206_H0.8")
      (libsource (lib "eagle-import") (part "WCAP-CSGP_1206_H0.8_50V(DC)_885012208087"))
    )
    (comp (ref "C32")
      (value "100nF")
      (footprint "eagle-import:WCAP-CSGP_1206_H0.8")
      (libsource (lib "eagle-import") (part "WCAP-CSGP_1206_H0.8_50V(DC)_885012208087"))
    )
    (comp (ref "C33")
      (value "100nF")
      (footprint "eagle-import:WCAP-CSGP_1206_H0.8")
      (libsource (lib "eagle-import") (part "WCAP-CSGP_1206_H0.8_50V(DC)_885012208087"))
    )
    (comp (ref "C34")
      (value "100nF")
      (footprint "eagle-import:WCAP-CSGP_1206_H0.8")
      (libsource (lib "eagle-import") (part "WCAP-CSGP_1206_H0.8_50V(DC)_885012208087"))
    )
    (comp (ref "D13")
      (value "3.3Vdc")
      (footprint "eagle-import:WE-TVS_SOT143-4L")
      (libsource (lib "eagle-import") (part "WE-TVS-HS_SOT143-4L_8240136"))
    )
    (comp (ref "R21")
      (value "1K2")
      (footprint "eagle-import:R1206")
      (libsource (lib "eagle-import") (part "R-EU_R1206"))
    )
    (comp (ref "R22")
      (value "47K")
      (footprint "eagle-import:R1206")
      (libsource (lib "eagle-import") (part "R-EU_R1206"))
    )
    (comp (ref "R23")
      (value "22K")
      (footprint "eagle-import:R1206")
      (libsource (lib "eagle-import") (part "R-EU_R1206"))
    )
    (comp (ref "R24")
      (value "1K2")
      (footprint "eagle-import:R1206")
      (libsource (lib "eagle-import") (part "R-EU_R1206"))
    )
    (comp (ref "R25")
      (value "47K")
      (footprint "eagle-import:R1206")
      (libsource (lib "eagle-import") (part "R-EU_R1206"))
    )
    (comp (ref "R26")
      (value "22K")
      (footprint "eagle-import:R1206")
      (libsource (lib "eagle-import") (part "R-EU_R1206"))
    )
    (comp (ref "J1")
      (value "638207222005")
      (footprint "eagle-import:638207222005")
      (libsource (lib "eagle-import") (part "638207222005"))
    )
    (comp (ref "J7")
      (value "638207222005")
      (footprint "eagle-import:638207222005")
      (libsource (lib "eagle-import") (part "638207222005"))
    )
    (comp (ref "J8")
      (value "638207222007")
      (footprint "eagle-import:638207222007")
      (libsource (lib "eagle-import") (part "638207222007"))
    )
    (comp (ref "J13")
      (value "638207222005")
      (footprint "eagle-import:638207222005")
      (libsource (lib "eagle-import") (part "638207222005"))
    )
    (comp (ref "J15")
      (value "638207222008")
      (footprint "eagle-import:638207222008")
      (libsource (lib "eagle-import") (part "638207222008"))
    )
    (comp (ref "C15")
      (value "47nF")
      (footprint "eagle-import:WCAP-CSGP_0805_H0.8_R")
      (libsource (lib "eagle-import") (part "WCAP-CSGP_0805_H0.8_50V(DC)_R_885012207096"))
    )
    (comp (ref "C17")
      (value "100nF")
      (footprint "eagle-import:WCAP-CSGP_0805_H0.8_R")
      (libsource (lib "eagle-import") (part "WCAP-CSGP_0805_H0.8_50V(DC)_R_885012207098"))
    )
    (comp (ref "C19")
      (value "100nF")
      (footprint "eagle-import:WCAP-CSGP_0805_H0.8_R")
      (libsource (lib "eagle-import") (part "WCAP-CSGP_0805_H0.8_50V(DC)_R_885012207098"))
    )
    (comp (ref "D11")
      (value "24Vdc")
      (footprint "eagle-import:WE-TVS_SOT23-3L")
      (libsource (lib "eagle-import") (part "WE-TVS_SOT23-3L_824094024"))
    )
    (comp (ref "R1")
      (value "60R")
      (footprint "eagle-import:R0805")
      (libsource (lib "eagle-import") (part "R-EU_R0805"))
    )
    (comp (ref "R3")
      (value "60R")
      (footprint "eagle-import:R0805")
      (libsource (lib "eagle-import") (part "R-EU_R0805"))
    )
    (comp (ref "U4")
      (value "TLE9250VSJ")
      (footprint "eagle-import:SOIC127P602X173-8N-V")
      (libsource (lib "eagle-import") (part "TLE9250VSJ"))
    )
    (comp (ref "C47")
      (value "100nF")
      (footprint "eagle-import:WCAP-CSGP_1206_H0.8")
      (libsource (lib "eagle-import") (part "WCAP-CSGP_1206_H0.8_50V(DC)_885012208087"))
    )
    (comp (ref "C48")
      (value "100nF")
      (footprint "eagle-import:WCAP-CSGP_1206_H0.8")
      (libsource (lib "eagle-import") (part "WCAP-CSGP_1206_H0.8_50V(DC)_885012208087"))
    )
    (comp (ref "C49")
      (value "100nF")
      (footprint "eagle-import:WCAP-CSGP_1206_H0.8")
      (libsource (lib "eagle-import") (part "WCAP-CSGP_1206_H0.8_50V(DC)_885012208087"))
    )
    (comp (ref "C50")
      (value "100nF")
      (footprint "eagle-import:WCAP-CSGP_1206_H0.8")
      (libsource (lib "eagle-import") (part "WCAP-CSGP_1206_H0.8_50V(DC)_885012208087"))
    )
    (comp (ref "D17")
      (value "3.3Vdc")
      (footprint "eagle-import:WE-TVS_SOT143-4L")
      (libsource (lib "eagle-import") (part "WE-TVS-HS_SOT143-4L_8240136"))
    )
    (comp (ref "R51")
      (value "1K2")
      (footprint "eagle-import:R1206")
      (libsource (lib "eagle-import") (part "R-EU_R1206"))
    )
    (comp (ref "R52")
      (value "47K")
      (footprint "eagle-import:R1206")
      (libsource (lib "eagle-import") (part "R-EU_R1206"))
    )
    (comp (ref "R53")
      (value "22K")
      (footprint "eagle-import:R1206")
      (libsource (lib "eagle-import") (part "R-EU_R1206"))
    )
    (comp (ref "R54")
      (value "1K2")
      (footprint "eagle-import:R1206")
      (libsource (lib "eagle-import") (part "R-EU_R1206"))
    )
    (comp (ref "R55")
      (value "47K")
      (footprint "eagle-import:R1206")
      (libsource (lib "eagle-import") (part "R-EU_R1206"))
    )
    (comp (ref "R56")
      (value "22K")
      (footprint "eagle-import:R1206")
      (libsource (lib "eagle-import") (part "R-EU_R1206"))
    )
    (comp (ref "C24")
      (value "100nF")
      (footprint "eagle-import:WCAP-CSGP_1206_H0.8")
      (libsource (lib "eagle-import") (part "WCAP-CSGP_1206_H0.8_50V(DC)_885012208087"))
    )
    (comp (ref "C25")
      (value "100nF")
      (footprint "eagle-import:WCAP-CSGP_1206_H0.8")
      (libsource (lib "eagle-import") (part "WCAP-CSGP_1206_H0.8_50V(DC)_885012208087"))
    )
    (comp (ref "C26")
      (value "100nF")
      (footprint "eagle-import:WCAP-CSGP_1206_H0.8")
      (libsource (lib "eagle-import") (part "WCAP-CSGP_1206_H0.8_50V(DC)_885012208087"))
    )
    (comp (ref "C27")
      (value "100nF")
      (footprint "eagle-import:WCAP-CSGP_1206_H0.8")
      (libsource (lib "eagle-import") (part "WCAP-CSGP_1206_H0.8_50V(DC)_885012208087"))
    )
    (comp (ref "D12")
      (value "3.3Vdc")
      (footprint "eagle-import:WE-TVS_SOT143-4L")
      (libsource (lib "eagle-import") (part "WE-TVS-HS_SOT143-4L_8240136"))
    )
    (comp (ref "R27")
      (value "1K2")
      (footprint "eagle-import:R1206")
      (libsource (lib "eagle-import") (part "R-EU_R1206"))
    )
    (comp (ref "R28")
      (value "1K2")
      (footprint "eagle-import:R1206")
      (libsource (lib "eagle-import") (part "R-EU_R1206"))
    )
    (comp (ref "R29")
      (value "47K")
      (footprint "eagle-import:R1206")
      (libsource (lib "eagle-import") (part "R-EU_R1206"))
    )
    (comp (ref "R30")
      (value "47K")
      (footprint "eagle-import:R1206")
      (libsource (lib "eagle-import") (part "R-EU_R1206"))
    )
    (comp (ref "R31")
      (value "22K")
      (footprint "eagle-import:R1206")
      (libsource (lib "eagle-import") (part "R-EU_R1206"))
    )
    (comp (ref "R32")
      (value "22K")
      (footprint "eagle-import:R1206")
      (libsource (lib "eagle-import") (part "R-EU_R1206"))
    )
    (comp (ref "C10")
      (value "22uF")
      (footprint "eagle-import:WCAP-CSGP_1210_H2.5")
      (libsource (lib "eagle-import") (part "WCAP-CSGP_1210_H2.5_25V(DC)_885012109014"))
    )
    (comp (ref "C12")
      (value "22uF")
      (footprint "eagle-import:WCAP-CSGP_0805_H1.25_R")
      (libsource (lib "eagle-import") (part "WCAP-CSGP_0805_H1.25_10V(DC)_885012107011"))
    )
    (comp (ref "C23")
      (value "330 µF")
      (footprint "eagle-import:WCAP-ASLI_12.5X14(DXL)")
      (libsource (lib "eagle-import") (part "WCAP-ASLI_12.5X14_865080662019"))
    )
    (comp (ref "D5")
      (value "33V")
      (footprint "eagle-import:WE-TVSP_DO-214AB_BIDIRECTIONAL")
      (libsource (lib "eagle-import") (part "WE-TVSP_DO-214AB_3000W_BI_824551331"))
    )
    (comp (ref "D006")
      (value "MBRS340T3")
      (footprint "eagle-import:SMC")
      (libsource (lib "eagle-import") (part "MBRS30T34"))
    )
    (comp (ref "G1")
      (value "IFX27001TF_V50")
      (footprint "eagle-import:INF-PG-TO252-3-11_N")
      (libsource (lib "eagle-import") (part "IFX27001TF_V50"))
    )
    (comp (ref "J2")
      (value "645004114822")
      (footprint "eagle-import:645004114822")
      (libsource (lib "eagle-import") (part "645004114822"))
    )
    (comp (ref "J4")
      (value "61300421121")
      (footprint "eagle-import:61300421121")
      (libsource (lib "eagle-import") (part "6130XX21121_61300421121"))
    )
    (comp (ref "ESP32-J1")
      (value "61302211821")
      (footprint "eagle-import:61302211821")
      (libsource (lib "eagle-import") (part "6130XX11821_61302211821"))
    )
    (comp (ref "ESP32-J3")
      (value "61302211821")
      (footprint "eagle-import:61302211821")
      (libsource (lib "eagle-import") (part "6130XX11821_61302211821"))
    )
    (comp (ref "R14")
      (value "13K")
      (footprint "eagle-import:R1206")
      (libsource (lib "eagle-import") (part "R-EU_R1206"))
    )
    (comp (ref "R15")
      (value "13K")
      (footprint "eagle-import:R1206")
      (libsource (lib "eagle-import") (part "R-EU_R1206"))
    )
    (comp (ref "R16")
      (value "13K")
      (footprint "eagle-import:R1206")
      (libsource (lib "eagle-import") (part "R-EU_R1206"))
    )
    (comp (ref "R17")
      (value "13K")
      (footprint "eagle-import:R1206")
      (libsource (lib "eagle-import") (part "R-EU_R1206"))
    )
    (comp (ref "R19")
      (value "13K")
      (footprint "eagle-import:R1206")
      (libsource (lib "eagle-import") (part "R-EU_R1206"))
    )
    (comp (ref "R20")
      (value "13K")
      (footprint "eagle-import:R1206")
      (libsource (lib "eagle-import") (part "R-EU_R1206"))
    )
    (comp (ref "R33")
      (value "13K")
      (footprint "eagle-import:R1206")
      (libsource (lib "eagle-import") (part "R-EU_R1206"))
    )
    (comp (ref "R34")
      (value "13K")
      (footprint "eagle-import:R1206")
      (libsource (lib "eagle-import") (part "R-EU_R1206"))
    )
    (comp (ref "RESET")
      (value "431256083736")
      (footprint "eagle-import:4312560837X6")
      (libsource (lib "eagle-import") (part "431256083736"))
    )
    (comp (ref "C1")
      (value "100nF")
      (footprint "eagle-import:WCAP-CSGP_0805_H0.8_R")
      (libsource (lib "eagle-import") (part "WCAP-CSGP_0805_H0.8_50V(DC)_R_885012207098"))
    )
    (comp (ref "C13")
      (value "100nF")
      (footprint "eagle-import:WCAP-CSGP_0805_H0.8_R")
      (libsource (lib "eagle-import") (part "WCAP-CSGP_0805_H0.8_50V(DC)_R_885012207098"))
    )
    (comp (ref "C14")
      (value "10nF")
      (footprint "eagle-import:WCAP-CSGP_0805_H0.8_R")
      (libsource (lib "eagle-import") (part "WCAP-CSGP_0805_H0.8_50V(DC)_R_885012207092"))
    )
    (comp (ref "C16")
      (value "10nF")
      (footprint "eagle-import:WCAP-CSGP_0805_H0.8_R")
      (libsource (lib "eagle-import") (part "WCAP-CSGP_0805_H0.8_50V(DC)_R_885012207092"))
    )
    (comp (ref "C18")
      (value "100nF")
      (footprint "eagle-import:WCAP-CSGP_0805_H0.8_R")
      (libsource (lib "eagle-import") (part "WCAP-CSGP_0805_H0.8_50V(DC)_R_885012207098"))
    )
    (comp (ref "C20")
      (value "100nF")
      (footprint "eagle-import:WCAP-CSGP_0805_H0.8_R")
      (libsource (lib "eagle-import") (part "WCAP-CSGP_0805_H0.8_50V(DC)_R_885012207098"))
    )
    (comp (ref "C21")
      (value "10nF")
      (footprint "eagle-import:WCAP-CSGP_0805_H0.8_R")
      (libsource (lib "eagle-import") (part "WCAP-CSGP_0805_H0.8_50V(DC)_R_885012207092"))
    )
    (comp (ref "C22")
      (value "10nF")
      (footprint "eagle-import:WCAP-CSGP_0805_H0.8_R")
      (libsource (lib "eagle-import") (part "WCAP-CSGP_0805_H0.8_50V(DC)_R_885012207092"))
    )
    (comp (ref "D7")
      (value "150141VS73100")
      (footprint "eagle-import:WL-SMTW_3528")
      (libsource (lib "eagle-import") (part "WL-SMTW_3528_150141VS73100"))
    )
    (comp (ref "D8")
      (value "150141VS73100")
      (footprint "eagle-import:WL-SMTW_3528")
      (libsource (lib "eagle-import") (part "WL-SMTW_3528_150141VS73100"))
    )
    (comp (ref "D9")
      (value "150141VS73100")
      (footprint "eagle-import:WL-SMTW_3528")
      (libsource (lib "eagle-import") (part "WL-SMTW_3528_150141VS73100"))
    )
    (comp (ref "D10")
      (value "150141VS73100")
      (footprint "eagle-import:WL-SMTW_3528")
      (libsource (lib "eagle-import") (part "WL-SMTW_3528_150141VS73100"))
    )
    (comp (ref "D020")
      (value "GS1J-L")
      (footprint "eagle-import:SMA_DO-214AC")
      (libsource (lib "eagle-import") (part "GS1-LJ"))
    )
    (comp (ref "D021")
      (value "GS1J-L")
      (footprint "eagle-import:SMA_DO-214AC")
      (libsource (lib "eagle-import") (part "GS1-LJ"))
    )
    (comp (ref "D022")
      (value "GS1J-L")
      (footprint "eagle-import:SMA_DO-214AC")
      (libsource (lib "eagle-import") (part "GS1-LJ"))
    )
    (comp (ref "D023")
      (value "GS1J-L")
      (footprint "eagle-import:SMA_DO-214AC")
      (libsource (lib "eagle-import") (part "GS1-LJ"))
    )
    (comp (ref "R5")
      (value "4k7")
      (footprint "eagle-import:R0805")
      (libsource (lib "eagle-import") (part "R-EU_R0805"))
    )
    (comp (ref "R6")
      (value "4k7")
      (footprint "eagle-import:R0805")
      (libsource (lib "eagle-import") (part "R-EU_R0805"))
    )
    (comp (ref "R8")
      (value "47R")
      (footprint "eagle-import:R0805")
      (libsource (lib "eagle-import") (part "R-EU_R0805"))
    )
    (comp (ref "R9")
      (value "4k7")
      (footprint "eagle-import:R0805")
      (libsource (lib "eagle-import") (part "R-EU_R0805"))
    )
    (comp (ref "R11")
      (value "4k7")
      (footprint "eagle-import:R0805")
      (libsource (lib "eagle-import") (part "R-EU_R0805"))
    )
    (comp (ref "R12")
      (value "47R")
      (footprint "eagle-import:R0805")
      (libsource (lib "eagle-import") (part "R-EU_R0805"))
    )
    (comp (ref "R37")
      (value "1k2")
      (footprint "eagle-import:R0805")
      (libsource (lib "eagle-import") (part "R-EU_R0805"))
    )
    (comp (ref "R38")
      (value "1k2")
      (footprint "eagle-import:R0805")
      (libsource (lib "eagle-import") (part "R-EU_R0805"))
    )
    (comp (ref "RX5")
      (value "470Ohm")
      (footprint "eagle-import:R1206")
      (libsource (lib "eagle-import") (part "R-EU_R1206"))
    )
    (comp (ref "RX6")
      (value "470Ohm")
      (footprint "eagle-import:R1206")
      (libsource (lib "eagle-import") (part "R-EU_R1206"))
    )
    (comp (ref "RX7")
      (value "470Ohm")
      (footprint "eagle-import:R1206")
      (libsource (lib "eagle-import") (part "R-EU_R1206"))
    )
    (comp (ref "RX8")
      (value "470Ohm")
      (footprint "eagle-import:R1206")
      (libsource (lib "eagle-import") (part "R-EU_R1206"))
    )
    (comp (ref "U5")
      (value "BTS7030-2EPA")
      (footprint "eagle-import:SOP65P600X115-15N-V")
      (libsource (lib "eagle-import") (part "BTS7030-2EPA"))
    )
    (comp (ref "U6")
      (value "BTS7030-2EPA")
      (footprint "eagle-import:SOP65P600X115-15N-V")
      (libsource (lib "eagle-import") (part "BTS7030-2EPA"))
    )
    (comp (ref "C39")
      (value "100nF")
      (footprint "eagle-import:WCAP-CSGP_1206_H0.8")
      (libsource (lib "eagle-import") (part "WCAP-CSGP_1206_H0.8_50V(DC)_885012208087"))
    )
    (comp (ref "C40")
      (value "100nF")
      (footprint "eagle-import:WCAP-CSGP_1206_H0.8")
      (libsource (lib "eagle-import") (part "WCAP-CSGP_1206_H0.8_50V(DC)_885012208087"))
    )
    (comp (ref "C41")
      (value "100nF")
      (footprint "eagle-import:WCAP-CSGP_1206_H0.8")
      (libsource (lib "eagle-import") (part "WCAP-CSGP_1206_H0.8_50V(DC)_885012208087"))
    )
    (comp (ref "C42")
      (value "100nF")
      (footprint "eagle-import:WCAP-CSGP_1206_H0.8")
      (libsource (lib "eagle-import") (part "WCAP-CSGP_1206_H0.8_50V(DC)_885012208087"))
    )
    (comp (ref "D15")
      (value "3.3Vdc")
      (footprint "eagle-import:WE-TVS_SOT143-4L")
      (libsource (lib "eagle-import") (part "WE-TVS-HS_SOT143-4L_8240136"))
    )
    (comp (ref "R39")
      (value "1K2")
      (footprint "eagle-import:R1206")
      (libsource (lib "eagle-import") (part "R-EU_R1206"))
    )
    (comp (ref "R40")
      (value "47K")
      (footprint "eagle-import:R1206")
      (libsource (lib "eagle-import") (part "R-EU_R1206"))
    )
    (comp (ref "R41")
      (value "22K")
      (footprint "eagle-import:R1206")
      (libsource (lib "eagle-import") (part "R-EU_R1206"))
    )
    (comp (ref "R42")
      (value "1K2")
      (footprint "eagle-import:R1206")
      (libsource (lib "eagle-import") (part "R-EU_R1206"))
    )
    (comp (ref "R43")
      (value "47K")
      (footprint "eagle-import:R1206")
      (libsource (lib "eagle-import") (part "R-EU_R1206"))
    )
    (comp (ref "R44")
      (value "22K")
      (footprint "eagle-import:R1206")
      (libsource (lib "eagle-import") (part "R-EU_R1206"))
    )
    (comp (ref "C2")
      (value "100nF")
      (footprint "eagle-import:WCAP-CSGP_0805_H0.8_R")
      (libsource (lib "eagle-import") (part "WCAP-CSGP_0805_H0.8_50V(DC)_R_885012207098"))
    )
    (comp (ref "C3")
      (value "100nF")
      (footprint "eagle-import:WCAP-CSGP_0805_H0.8_R")
      (libsource (lib "eagle-import") (part "WCAP-CSGP_0805_H0.8_50V(DC)_R_885012207098"))
    )
    (comp (ref "C4")
      (value "10nF")
      (footprint "eagle-import:WCAP-CSGP_0805_H0.8_R")
      (libsource (lib "eagle-import") (part "WCAP-CSGP_0805_H0.8_50V(DC)_R_885012207092"))
    )
    (comp (ref "C5")
      (value "100nF")
      (footprint "eagle-import:WCAP-CSGP_0805_H0.8_R")
      (libsource (lib "eagle-import") (part "WCAP-CSGP_0805_H0.8_50V(DC)_R_885012207098"))
    )
    (comp (ref "C6")
      (value "100nF")
      (footprint "eagle-import:WCAP-CSGP_0805_H0.8_R")
      (libsource (lib "eagle-import") (part "WCAP-CSGP_0805_H0.8_50V(DC)_R_885012207098"))
    )
    (comp (ref "C7")
      (value "10nF")
      (footprint "eagle-import:WCAP-CSGP_0805_H0.8_R")
      (libsource (lib "eagle-import") (part "WCAP-CSGP_0805_H0.8_50V(DC)_R_885012207092"))
    )
    (comp (ref "C8")
      (value "10nF")
      (footprint "eagle-import:WCAP-CSGP_0805_H0.8_R")
      (libsource (lib "eagle-import") (part "WCAP-CSGP_0805_H0.8_50V(DC)_R_885012207092"))
    )
    (comp (ref "C9")
      (value "10nF")
      (footprint "eagle-import:WCAP-CSGP_0805_H0.8_R")
      (libsource (lib "eagle-import") (part "WCAP-CSGP_0805_H0.8_50V(DC)_R_885012207092"))
    )
    (comp (ref "D0")
      (value "33V")
      (footprint "eagle-import:WE-TVSP_DO-214AB_BIDIRECTIONAL")
      (libsource (lib "eagle-import") (part "WE-TVSP_DO-214AB_3000W_BI_824551331"))
    )
    (comp (ref "D1")
      (value "150141VS73100")
      (footprint "eagle-import:WL-SMTW_3528")
      (libsource (lib "eagle-import") (part "WL-SMTW_3528_150141VS73100"))
    )
    (comp (ref "D2")
      (value "150141VS73100")
      (footprint "eagle-import:WL-SMTW_3528")
      (libsource (lib "eagle-import") (part "WL-SMTW_3528_150141VS73100"))
    )
    (comp (ref "D3")
      (value "150141VS73100")
      (footprint "eagle-import:WL-SMTW_3528")
      (libsource (lib "eagle-import") (part "WL-SMTW_3528_150141VS73100"))
    )
    (comp (ref "D4")
      (value "150141VS73100")
      (footprint "eagle-import:WL-SMTW_3528")
      (libsource (lib "eagle-import") (part "WL-SMTW_3528_150141VS73100"))
    )
    (comp (ref "D014")
      (value "GS1J-L")
      (footprint "eagle-import:SMA_DO-214AC")
      (libsource (lib "eagle-import") (part "GS1-LJ"))
    )
    (comp (ref "D016")
      (value "GS1J-L")
      (footprint "eagle-import:SMA_DO-214AC")
      (libsource (lib "eagle-import") (part "GS1-LJ"))
    )
    (comp (ref "D018")
      (value "GS1J-L")
      (footprint "eagle-import:SMA_DO-214AC")
      (libsource (lib "eagle-import") (part "GS1-LJ"))
    )
    (comp (ref "D019")
      (value "GS1J-L")
      (footprint "eagle-import:SMA_DO-214AC")
      (libsource (lib "eagle-import") (part "GS1-LJ"))
    )
    (comp (ref "J5")
      (value "6130XX21121_61300621121")
      (footprint "eagle-import:61300621121")
      (libsource (lib "eagle-import") (part "6130XX21121_61300621121"))
    )
    (comp (ref "J9")
      (value "6130XX21121_61300621121")
      (footprint "eagle-import:61300621121")
      (libsource (lib "eagle-import") (part "6130XX21121_61300621121"))
    )
    (comp (ref "R2")
      (value "4k7")
      (footprint "eagle-import:R0805")
      (libsource (lib "eagle-import") (part "R-EU_R0805"))
    )
    (comp (ref "R4")
      (value "4k7")
      (footprint "eagle-import:R0805")
      (libsource (lib "eagle-import") (part "R-EU_R0805"))
    )
    (comp (ref "R7")
      (value "47R")
      (footprint "eagle-import:R0805")
      (libsource (lib "eagle-import") (part "R-EU_R0805"))
    )
    (comp (ref "R10")
      (value "47R")
      (footprint "eagle-import:R0805")
      (libsource (lib "eagle-import") (part "R-EU_R0805"))
    )
    (comp (ref "R13")
      (value "4k7")
      (footprint "eagle-import:R0805")
      (libsource (lib "eagle-import") (part "R-EU_R0805"))
    )
    (comp (ref "R18")
      (value "4k7")
      (footprint "eagle-import:R0805")
      (libsource (lib "eagle-import") (part "R-EU_R0805"))
    )
    (comp (ref "R35")
      (value "1k2")
      (footprint "eagle-import:R0805")
      (libsource (lib "eagle-import") (part "R-EU_R0805"))
    )
    (comp (ref "R36")
      (value "1k2")
      (footprint "eagle-import:R0805")
      (libsource (lib "eagle-import") (part "R-EU_R0805"))
    )
    (comp (ref "RX1")
      (value "470Ohm")
      (footprint "eagle-import:R1206")
      (libsource (lib "eagle-import") (part "R-EU_R1206"))
    )
    (comp (ref "RX2")
      (value "470Ohm")
      (footprint "eagle-import:R1206")
      (libsource (lib "eagle-import") (part "R-EU_R1206"))
    )
    (comp (ref "RX3")
      (value "470Ohm")
      (footprint "eagle-import:R1206")
      (libsource (lib "eagle-import") (part "R-EU_R1206"))
    )
    (comp (ref "RX4")
      (value "470Ohm")
      (footprint "eagle-import:R1206")
      (libsource (lib "eagle-import") (part "R-EU_R1206"))
    )
    (comp (ref "U2")
      (value "BTS7030-2EPA")
      (footprint "eagle-import:SOP65P600X115-15N-V")
      (libsource (lib "eagle-import") (part "BTS7030-2EPA"))
    )
    (comp (ref "U3")
      (value "BTS7030-2EPA")
      (footprint "eagle-import:SOP65P600X115-15N-V")
      (libsource (lib "eagle-import") (part "BTS7030-2EPA"))
    )
  )
  (nets
    (net (code "1") (name "+3V3") (class "Default")
      (node (ref "C19") (pin "1") (pinfunction "1_1") (pintype "passive"))
      (node (ref "D12") (pin "4") (pinfunction "VDD_4") (pintype "passive"))
      (node (ref "D13") (pin "4") (pinfunction "VDD_4") (pintype "passive"))
      (node (ref "D15") (pin "4") (pinfunction "VDD_4") (pintype "passive"))
      (node (ref "D17") (pin "4") (pinfunction "VDD_4") (pintype "passive"))
      (node (ref "ESP32-J1") (pin "1") (pinfunction "1_1") (pintype "passive"))
      (node (ref "ESP32-J1") (pin "2") (pinfunction "2_2") (pintype "passive"))
      (node (ref "U4") (pin "5") (pinfunction "VIO_5") (pintype "input"))
    )
    (net (code "2") (name "+5V") (class "Default")
      (node (ref "C12") (pin "2") (pinfunction "2_2") (pintype "passive"))
      (node (ref "C17") (pin "1") (pinfunction "1_1") (pintype "passive"))
      (node (ref "ESP32-J1") (pin "21") (pinfunction "21_21") (pintype "passive"))
      (node (ref "G1") (pin "2") (pinfunction "Q_2") (pintype "power_in"))
      (node (ref "J4") (pin "1") (pinfunction "1_1") (pintype "passive"))
      (node (ref "J4") (pin "2") (pinfunction "2_2") (pintype "passive"))
      (node (ref "J4") (pin "3") (pinfunction "3_3") (pintype "passive"))
      (node (ref "J4") (pin "4") (pinfunction "4_4") (pintype "passive"))
      (node (ref "U4") (pin "3") (pinfunction "VCC_3") (pintype "input"))
    )
    (net (code "3") (name "AGNDU2") (class "Default")
      (node (ref "C6") (pin "2") (pinfunction "2_2") (pintype "passive"))
      (node (ref "R10") (pin "2") (pinfunction "2_2") (pintype "passive"))
      (node (ref "U2") (pin "1") (pinfunction "GND_1") (pintype "power_in"))
    )
    (net (code "4") (name "AGNDU3") (class "Default")
      (node (ref "C3") (pin "2") (pinfunction "2_2") (pintype "passive"))
      (node (ref "R7") (pin "2") (pinfunction "2_2") (pintype "passive"))
      (node (ref "U3") (pin "1") (pinfunction "GND_1") (pintype "power_in"))
    )
    (net (code "5") (name "AGNDU4") (class "Default")
      (node (ref "C13") (pin "2") (pinfunction "2_2") (pintype "passive"))
      (node (ref "R8") (pin "2") (pinfunction "2_2") (pintype "passive"))
      (node (ref "U5") (pin "1") (pinfunction "GND_1") (pintype "power_in"))
    )
    (net (code "6") (name "AGNDU5") (class "Default")
      (node (ref "C20") (pin "2") (pinfunction "2_2") (pintype "passive"))
      (node (ref "R12") (pin "2") (pinfunction "2_2") (pintype "passive"))
      (node (ref "U6") (pin "1") (pinfunction "GND_1") (pintype "power_in"))
    )
    (net (code "7") (name "BOOT") (class "Default")
      (node (ref "ESP32-J3") (pin "14") (pinfunction "14_14") (pintype "passive"))
    )
    (net (code "8") (name "CAN1_RXD") (class "Default")
      (node (ref "ESP32-J1") (pin "5") (pinfunction "5_5") (pintype "passive"))
      (node (ref "U4") (pin "4") (pinfunction "RXD_4") (pintype "output"))
    )
    (net (code "9") (name "CAN1_TXD") (class "Default")
      (node (ref "ESP32-J1") (pin "4") (pinfunction "4_4") (pintype "passive"))
      (node (ref "U4") (pin "1") (pinfunction "TXD_1") (pintype "input"))
    )
    (net (code "10") (name "CAN_N") (class "Default")
      (node (ref "D11") (pin "1") (pinfunction "I/O1_1") (pintype "passive"))
      (node (ref "J2") (pin "1") (pinfunction "1_1") (pintype "passive"))
      (node (ref "R3") (pin "2") (pinfunction "2_2") (pintype "passive"))
      (node (ref "U4") (pin "6") (pinfunction "CANL_6") (pintype "bidirectional"))
    )
    (net (code "11") (name "CAN_P") (class "Default")
      (node (ref "D11") (pin "2") (pinfunction "I/O2_2") (pintype "passive"))
      (node (ref "J2") (pin "2") (pinfunction "2_2") (pintype "passive"))
      (node (ref "R1") (pin "2") (pinfunction "2_2") (pintype "passive"))
      (node (ref "U4") (pin "7") (pinfunction "CANH_7") (pintype "bidirectional"))
    )
    (net (code "12") (name "CI1") (class "Default")
      (node (ref "C32") (pin "1") (pinfunction "1_1") (pintype "passive"))
      (node (ref "D13") (pin "3") (pinfunction "2_3") (pintype "passive"))
      (node (ref "ESP32-J1") (pin "19") (pinfunction "19_19") (pintype "passive"))
      (node (ref "R22") (pin "1") (pinfunction "1_1") (pintype "passive"))
      (node (ref "R23") (pin "2") (pinfunction "2_2") (pintype "passive"))
    )
    (net (code "13") (name "CI2") (class "Default")
      (node (ref "C34") (pin "1") (pinfunction "1_1") (pintype "passive"))
      (node (ref "D13") (pin "2") (pinfunction "1_2") (pintype "passive"))
      (node (ref "ESP32-J1") (pin "18") (pinfunction "18_18") (pintype "passive"))
      (node (ref "R25") (pin "1") (pinfunction "1_1") (pintype "passive"))
      (node (ref "R26") (pin "2") (pinfunction "2_2") (pintype "passive"))
    )
    (net (code "14") (name "CI3") (class "Default")
      (node (ref "C40") (pin "1") (pinfunction "1_1") (pintype "passive"))
      (node (ref "D15") (pin "3") (pinfunction "2_3") (pintype "passive"))
      (node (ref "ESP32-J1") (pin "15") (pinfunction "15_15") (pintype "passive"))
      (node (ref "R40") (pin "1") (pinfunction "1_1") (pintype "passive"))
      (node (ref "R41") (pin "2") (pinfunction "2_2") (pintype "passive"))
    )
    (net (code "15") (name "CI4") (class "Default")
      (node (ref "C42") (pin "1") (pinfunction "1_1") (pintype "passive"))
      (node (ref "D15") (pin "2") (pinfunction "1_2") (pintype "passive"))
      (node (ref "ESP32-J1") (pin "13") (pinfunction "13_13") (pintype "passive"))
      (node (ref "R43") (pin "1") (pinfunction "1_1") (pintype "passive"))
      (node (ref "R44") (pin "2") (pinfunction "2_2") (pintype "passive"))
    )
    (net (code "16") (name "CI5") (class "Default")
      (node (ref "C48") (pin "1") (pinfunction "1_1") (pintype "passive"))
      (node (ref "D17") (pin "3") (pinfunction "2_3") (pintype "passive"))
      (node (ref "ESP32-J1") (pin "11") (pinfunction "11_11") (pintype "passive"))
      (node (ref "R52") (pin "1") (pinfunction "1_1") (pintype "passive"))
      (node (ref "R53") (pin "2") (pinfunction "2_2") (pintype "passive"))
    )
    (net (code "17") (name "CI6") (class "Default")
      (node (ref "C50") (pin "1") (pinfunction "1_1") (pintype "passive"))
      (node (ref "D17") (pin "2") (pinfunction "1_2") (pintype "passive"))
      (node (ref "ESP32-J1") (pin "10") (pinfunction "10_10") (pintype "passive"))
      (node (ref "R55") (pin "1") (pinfunction "1_1") (pintype "passive"))
      (node (ref "R56") (pin "2") (pinfunction "2_2") (pintype "passive"))
    )
    (net (code "18") (name "CI7") (class "Default")
      (node (ref "C27") (pin "1") (pinfunction "1_1") (pintype "passive"))
      (node (ref "D12") (pin "3") (pinfunction "2_3") (pintype "passive"))
      (node (ref "ESP32-J1") (pin "7") (pinfunction "7_7") (pintype "passive"))
      (node (ref "R30") (pin "1") (pinfunction "1_1") (pintype "passive"))
      (node (ref "R32") (pin "2") (pinfunction "2_2") (pintype "passive"))
    )
    (net (code "19") (name "CI8") (class "Default")
      (node (ref "C26") (pin "1") (pinfunction "1_1") (pintype "passive"))
      (node (ref "D12") (pin "2") (pinfunction "1_2") (pintype "passive"))
      (node (ref "ESP32-J1") (pin "6") (pinfunction "6_6") (pintype "passive"))
      (node (ref "R29") (pin "1") (pinfunction "1_1") (pintype "passive"))
      (node (ref "R31") (pin "2") (pinfunction "2_2") (pintype "passive"))
    )
    (net (code "20") (name "ECU_GND") (class "Default")
      (node (ref "C1") (pin "2") (pinfunction "2_2") (pintype "passive"))
      (node (ref "C10") (pin "1") (pinfunction "1_1") (pintype "passive"))
      (node (ref "C12") (pin "1") (pinfunction "1_1") (pintype "passive"))
      (node (ref "C15") (pin "2") (pinfunction "2_2") (pintype "passive"))
      (node (ref "C17") (pin "2") (pinfunction "2_2") (pintype "passive"))
      (node (ref "C18") (pin "2") (pinfunction "2_2") (pintype "passive"))
      (node (ref "C19") (pin "2") (pinfunction "2_2") (pintype "passive"))
      (node (ref "C2") (pin "2") (pinfunction "2_2") (pintype "passive"))
      (node (ref "C23") (pin "2") (pinfunction "-_2") (pintype "passive"))
      (node (ref "C24") (pin "2") (pinfunction "2_2") (pintype "passive"))
      (node (ref "C25") (pin "2") (pinfunction "2_2") (pintype "passive"))
      (node (ref "C26") (pin "2") (pinfunction "2_2") (pintype "passive"))
      (node (ref "C27") (pin "2") (pinfunction "2_2") (pintype "passive"))
      (node (ref "C31") (pin "2") (pinfunction "2_2") (pintype "passive"))
      (node (ref "C32") (pin "2") (pinfunction "2_2") (pintype "passive"))
      (node (ref "C33") (pin "2") (pinfunction "2_2") (pintype "passive"))
      (node (ref "C34") (pin "2") (pinfunction "2_2") (pintype "passive"))
      (node (ref "C39") (pin "2") (pinfunction "2_2") (pintype "passive"))
      (node (ref "C40") (pin "2") (pinfunction "2_2") (pintype "passive"))
      (node (ref "C41") (pin "2") (pinfunction "2_2") (pintype "passive"))
      (node (ref "C42") (pin "2") (pinfunction "2_2") (pintype "passive"))
      (node (ref "C47") (pin "2") (pinfunction "2_2") (pintype "passive"))
      (node (ref "C48") (pin "2") (pinfunction "2_2") (pintype "passive"))
      (node (ref "C49") (pin "2") (pinfunction "2_2") (pintype "passive"))
      (node (ref "C5") (pin "2") (pinfunction "2_2") (pintype "passive"))
      (node (ref "C50") (pin "2") (pinfunction "2_2") (pintype "passive"))
      (node (ref "D11") (pin "3") (pinfunction "GND_3") (pintype "passive"))
      (node (ref "D12") (pin "1") (pinfunction "GND_1") (pintype "passive"))
      (node (ref "D13") (pin "1") (pinfunction "GND_1") (pintype "passive"))
      (node (ref "D15") (pin "1") (pinfunction "GND_1") (pintype "passive"))
      (node (ref "D17") (pin "1") (pinfunction "GND_1") (pintype "passive"))
      (node (ref "D5") (pin "1") (pinfunction "1_1") (pintype "passive"))
      (node (ref "ESP32-J1") (pin "22") (pinfunction "22_22") (pintype "passive"))
      (node (ref "ESP32-J3") (pin "1") (pinfunction "1_1") (pintype "passive"))
      (node (ref "ESP32-J3") (pin "21") (pinfunction "21_21") (pintype "passive"))
      (node (ref "ESP32-J3") (pin "22") (pinfunction "22_22") (pintype "passive"))
      (node (ref "G1") (pin "1") (pinfunction "GND/ADJ_1") (pintype "power_in"))
      (node (ref "J2") (pin "4") (pinfunction "4_4") (pintype "passive"))
      (node (ref "J7") (pin "1") (pinfunction "1_1") (pintype "passive"))
      (node (ref "J7") (pin "2") (pinfunction "2_2") (pintype "passive"))
      (node (ref "J7") (pin "A1") (pinfunction "1_A1") (pintype "passive"))
      (node (ref "J7") (pin "A2") (pinfunction "2_A2") (pintype "passive"))
      (node (ref "J9") (pin "2") (pinfunction "2_2") (pintype "passive"))
      (node (ref "J9") (pin "4") (pinfunction "4_4") (pintype "passive"))
      (node (ref "J9") (pin "6") (pinfunction "6_6") (pintype "passive"))
      (node (ref "R10") (pin "1") (pinfunction "1_1") (pintype "passive"))
      (node (ref "R12") (pin "1") (pinfunction "1_1") (pintype "passive"))
      (node (ref "R14") (pin "1") (pinfunction "1_1") (pintype "passive"))
      (node (ref "R15") (pin "1") (pinfunction "1_1") (pintype "passive"))
      (node (ref "R16") (pin "1") (pinfunction "1_1") (pintype "passive"))
      (node (ref "R17") (pin "1") (pinfunction "1_1") (pintype "passive"))
      (node (ref "R19") (pin "1") (pinfunction "1_1") (pintype "passive"))
      (node (ref "R20") (pin "1") (pinfunction "1_1") (pintype "passive"))
      (node (ref "R21") (pin "1") (pinfunction "1_1") (pintype "passive"))
      (node (ref "R23") (pin "1") (pinfunction "1_1") (pintype "passive"))
      (node (ref "R24") (pin "1") (pinfunction "1_1") (pintype "passive"))
      (node (ref "R26") (pin "1") (pinfunction "1_1") (pintype "passive"))
      (node (ref "R27") (pin "1") (pinfunction "1_1") (pintype "passive"))
      (node (ref "R28") (pin "1") (pinfunction "1_1") (pintype "passive"))
      (node (ref "R31") (pin "1") (pinfunction "1_1") (pintype "passive"))
      (node (ref "R32") (pin "1") (pinfunction "1_1") (pintype "passive"))
      (node (ref "R33") (pin "1") (pinfunction "1_1") (pintype "passive"))
      (node (ref "R34") (pin "1") (pinfunction "1_1") (pintype "passive"))
      (node (ref "R35") (pin "1") (pinfunction "1_1") (pintype "passive"))
      (node (ref "R36") (pin "1") (pinfunction "1_1") (pintype "passive"))
      (node (ref "R37") (pin "1") (pinfunction "1_1") (pintype "passive"))
      (node (ref "R38") (pin "1") (pinfunction "1_1") (pintype "passive"))
      (node (ref "R39") (pin "1") (pinfunction "1_1") (pintype "passive"))
      (node (ref "R41") (pin "1") (pinfunction "1_1") (pintype "passive"))
      (node (ref "R42") (pin "1") (pinfunction "1_1") (pintype "passive"))
      (node (ref "R44") (pin "1") (pinfunction "1_1") (pintype "passive"))
      (node (ref "R51") (pin "1") (pinfunction "1_1") (pintype "passive"))
      (node (ref "R53") (pin "1") (pinfunction "1_1") (pintype "passive"))
      (node (ref "R54") (pin "1") (pinfunction "1_1") (pintype "passive"))
      (node (ref "R56") (pin "1") (pinfunction "1_1") (pintype "passive"))
      (node (ref "R7") (pin "1") (pinfunction "1_1") (pintype "passive"))
      (node (ref "R8") (pin "1") (pinfunction "1_1") (pintype "passive"))
      (node (ref "RESET") (pin "1") (pinfunction "GND1_1") (pintype "passive"))
      (node (ref "RESET") (pin "2") (pinfunction "2_2") (pintype "passive"))
      (node (ref "RESET") (pin "4") (pinfunction "GND_4") (pintype "passive"))
      (node (ref "U4") (pin "2") (pinfunction "GND_2") (pintype "power_in"))
      (node (ref "U4") (pin "8") (pinfunction "NEN_8") (pintype "input"))
    )
    (net (code "21") (name "ECU_PWR") (class "Default")
      (node (ref "D006") (pin "A") (pinfunction "A_A") (pintype "passive"))
      (node (ref "D5") (pin "2") (pinfunction "2_2") (pintype "passive"))
      (node (ref "J2") (pin "3") (pinfunction "3_3") (pintype "passive"))
      (node (ref "J5") (pin "2") (pinfunction "2_2") (pintype "passive"))
      (node (ref "J5") (pin "4") (pinfunction "4_4") (pintype "passive"))
      (node (ref "J5") (pin "6") (pinfunction "6_6") (pintype "passive"))
      (node (ref "J7") (pin "3") (pinfunction "3_3") (pintype "passive"))
      (node (ref "J7") (pin "4") (pinfunction "4_4") (pintype "passive"))
      (node (ref "J7") (pin "A3") (pinfunction "3_A3") (pintype "passive"))
      (node (ref "J7") (pin "A4") (pinfunction "4_A4") (pintype "passive"))
    )
    (net (code "22") (name "I1") (class "Default")
      (node (ref "C31") (pin "1") (pinfunction "1_1") (pintype "passive"))
      (node (ref "J7") (pin "5") (pinfunction "5_5") (pintype "passive"))
      (node (ref "J7") (pin "A5") (pinfunction "5_A5") (pintype "passive"))
      (node (ref "R21") (pin "2") (pinfunction "2_2") (pintype "passive"))
      (node (ref "R22") (pin "2") (pinfunction "2_2") (pintype "passive"))
    )
    (net (code "23") (name "I2") (class "Default")
      (node (ref "C33") (pin "1") (pinfunction "1_1") (pintype "passive"))
      (node (ref "J8") (pin "1") (pinfunction "1_1") (pintype "passive"))
      (node (ref "J8") (pin "A1") (pinfunction "1_A1") (pintype "passive"))
      (node (ref "R24") (pin "2") (pinfunction "2_2") (pintype "passive"))
      (node (ref "R25") (pin "2") (pinfunction "2_2") (pintype "passive"))
    )
    (net (code "24") (name "I3") (class "Default")
      (node (ref "C39") (pin "1") (pinfunction "1_1") (pintype "passive"))
      (node (ref "J8") (pin "2") (pinfunction "2_2") (pintype "passive"))
      (node (ref "J8") (pin "A2") (pinfunction "2_A2") (pintype "passive"))
      (node (ref "R39") (pin "2") (pinfunction "2_2") (pintype "passive"))
      (node (ref "R40") (pin "2") (pinfunction "2_2") (pintype "passive"))
    )
    (net (code "25") (name "I4") (class "Default")
      (node (ref "C41") (pin "1") (pinfunction "1_1") (pintype "passive"))
      (node (ref "J8") (pin "3") (pinfunction "3_3") (pintype "passive"))
      (node (ref "J8") (pin "A3") (pinfunction "3_A3") (pintype "passive"))
      (node (ref "R42") (pin "2") (pinfunction "2_2") (pintype "passive"))
      (node (ref "R43") (pin "2") (pinfunction "2_2") (pintype "passive"))
    )
    (net (code "26") (name "I5") (class "Default")
      (node (ref "C47") (pin "1") (pinfunction "1_1") (pintype "passive"))
      (node (ref "J8") (pin "4") (pinfunction "4_4") (pintype "passive"))
      (node (ref "J8") (pin "A4") (pinfunction "4_A4") (pintype "passive"))
      (node (ref "R51") (pin "2") (pinfunction "2_2") (pintype "passive"))
      (node (ref "R52") (pin "2") (pinfunction "2_2") (pintype "passive"))
    )
    (net (code "27") (name "I6") (class "Default")
      (node (ref "C49") (pin "1") (pinfunction "1_1") (pintype "passive"))
      (node (ref "J8") (pin "5") (pinfunction "5_5") (pintype "passive"))
      (node (ref "J8") (pin "A5") (pinfunction "5_A5") (pintype "passive"))
      (node (ref "R54") (pin "2") (pinfunction "2_2") (pintype "passive"))
      (node (ref "R55") (pin "2") (pinfunction "2_2") (pintype "passive"))
    )
    (net (code "28") (name "I7") (class "Default")
      (node (ref "C25") (pin "1") (pinfunction "1_1") (pintype "passive"))
      (node (ref "J8") (pin "6") (pinfunction "6_6") (pintype "passive"))
      (node (ref "J8") (pin "A6") (pinfunction "6_A6") (pintype "passive"))
      (node (ref "R28") (pin "2") (pinfunction "2_2") (pintype "passive"))
      (node (ref "R30") (pin "2") (pinfunction "2_2") (pintype "passive"))
    )
    (net (code "29") (name "I8") (class "Default")
      (node (ref "C24") (pin "1") (pinfunction "1_1") (pintype "passive"))
      (node (ref "J8") (pin "7") (pinfunction "7_7") (pintype "passive"))
      (node (ref "J8") (pin "A7") (pinfunction "7_A7") (pintype "passive"))
      (node (ref "R27") (pin "2") (pinfunction "2_2") (pintype "passive"))
      (node (ref "R29") (pin "2") (pinfunction "2_2") (pintype "passive"))
    )
    (net (code "30") (name "Net-(C15-Pad1)") (class "Default")
      (node (ref "C15") (pin "1") (pinfunction "1_1") (pintype "passive"))
      (node (ref "R1") (pin "1") (pinfunction "1_1") (pintype "passive"))
      (node (ref "R3") (pin "1") (pinfunction "1_1") (pintype "passive"))
    )
    (net (code "31") (name "Net-(C23-+)") (class "Default")
      (node (ref "C10") (pin "2") (pinfunction "2_2") (pintype "passive"))
      (node (ref "C23") (pin "1") (pinfunction "+_1") (pintype "passive"))
      (node (ref "D006") (pin "C") (pinfunction "C_C") (pintype "passive"))
      (node (ref "G1") (pin "3") (pinfunction "I_3") (pintype "power_in"))
    )
    (net (code "32") (name "Net-(D1--)") (class "Default")
      (node (ref "D1") (pin "1") (pinfunction "-_1") (pintype "passive"))
      (node (ref "RX1") (pin "2") (pinfunction "2_2") (pintype "passive"))
    )
    (net (code "33") (name "Net-(D2--)") (class "Default")
      (node (ref "D2") (pin "1") (pinfunction "-_1") (pintype "passive"))
      (node (ref "RX2") (pin "1") (pinfunction "1_1") (pintype "passive"))
    )
    (net (code "34") (name "Net-(D3--)") (class "Default")
      (node (ref "D3") (pin "1") (pinfunction "-_1") (pintype "passive"))
      (node (ref "RX3") (pin "2") (pinfunction "2_2") (pintype "passive"))
    )
    (net (code "35") (name "Net-(D4--)") (class "Default")
      (node (ref "D4") (pin "1") (pinfunction "-_1") (pintype "passive"))
      (node (ref "RX4") (pin "1") (pinfunction "1_1") (pintype "passive"))
    )
    (net (code "36") (name "Net-(D7--)") (class "Default")
      (node (ref "D7") (pin "1") (pinfunction "-_1") (pintype "passive"))
      (node (ref "RX6") (pin "1") (pinfunction "1_1") (pintype "passive"))
    )
    (net (code "37") (name "Net-(D8--)") (class "Default")
      (node (ref "D8") (pin "1") (pinfunction "-_1") (pintype "passive"))
      (node (ref "RX7") (pin "2") (pinfunction "2_2") (pintype "passive"))
    )
    (net (code "38") (name "Net-(D9--)") (class "Default")
      (node (ref "D9") (pin "1") (pinfunction "-_1") (pintype "passive"))
      (node (ref "RX5") (pin "1") (pinfunction "1_1") (pintype "passive"))
    )
    (net (code "39") (name "Net-(D10--)") (class "Default")
      (node (ref "D10") (pin "1") (pinfunction "-_1") (pintype "passive"))
      (node (ref "RX8") (pin "2") (pinfunction "2_2") (pintype "passive"))
    )
    (net (code "40") (name "Net-(U2-IN0)") (class "Default")
      (node (ref "R18") (pin "2") (pinfunction "2_2") (pintype "passive"))
      (node (ref "U2") (pin "2") (pinfunction "IN0_2") (pintype "input"))
    )
    (net (code "41") (name "Net-(U2-IN1)") (class "Default")
      (node (ref "R13") (pin "2") (pinfunction "2_2") (pintype "passive"))
      (node (ref "U2") (pin "6") (pinfunction "IN1_6") (pintype "input"))
    )
    (net (code "42") (name "Net-(U3-IN0)") (class "Default")
      (node (ref "R2") (pin "2") (pinfunction "2_2") (pintype "passive"))
      (node (ref "U3") (pin "2") (pinfunction "IN0_2") (pintype "input"))
    )
    (net (code "43") (name "Net-(U3-IN1)") (class "Default")
      (node (ref "R4") (pin "2") (pinfunction "2_2") (pintype "passive"))
      (node (ref "U3") (pin "6") (pinfunction "IN1_6") (pintype "input"))
    )
    (net (code "44") (name "Net-(U5-IN0)") (class "Default")
      (node (ref "R5") (pin "2") (pinfunction "2_2") (pintype "passive"))
      (node (ref "U5") (pin "2") (pinfunction "IN0_2") (pintype "input"))
    )
    (net (code "45") (name "Net-(U5-IN1)") (class "Default")
      (node (ref "R6") (pin "2") (pinfunction "2_2") (pintype "passive"))
      (node (ref "U5") (pin "6") (pinfunction "IN1_6") (pintype "input"))
    )
    (net (code "46") (name "Net-(U6-IN0)") (class "Default")
      (node (ref "R9") (pin "2") (pinfunction "2_2") (pintype "passive"))
      (node (ref "U6") (pin "2") (pinfunction "IN0_2") (pintype "input"))
    )
    (net (code "47") (name "Net-(U6-IN1)") (class "Default")
      (node (ref "R11") (pin "2") (pinfunction "2_2") (pintype "passive"))
      (node (ref "U6") (pin "6") (pinfunction "IN1_6") (pintype "input"))
    )
    (net (code "48") (name "PWR") (class "Default")
      (node (ref "C1") (pin "1") (pinfunction "1_1") (pintype "passive"))
      (node (ref "C13") (pin "1") (pinfunction "1_1") (pintype "passive"))
      (node (ref "C18") (pin "1") (pinfunction "1_1") (pintype "passive"))
      (node (ref "C2") (pin "1") (pinfunction "1_1") (pintype "passive"))
      (node (ref "C20") (pin "1") (pinfunction "1_1") (pintype "passive"))
      (node (ref "C3") (pin "1") (pinfunction "1_1") (pintype "passive"))
      (node (ref "C5") (pin "1") (pinfunction "1_1") (pintype "passive"))
      (node (ref "C6") (pin "1") (pinfunction "1_1") (pintype "passive"))
      (node (ref "D0") (pin "2") (pinfunction "2_2") (pintype "passive"))
      (node (ref "J13") (pin "4") (pinfunction "4_4") (pintype "passive"))
      (node (ref "J13") (pin "A4") (pinfunction "4_A4") (pintype "passive"))
      (node (ref "J5") (pin "1") (pinfunction "1_1") (pintype "passive"))
      (node (ref "J5") (pin "3") (pinfunction "3_3") (pintype "passive"))
      (node (ref "J5") (pin "5") (pinfunction "5_5") (pintype "passive"))
      (node (ref "U2") (pin "15") (pinfunction "VS_15") (pintype "power_in"))
      (node (ref "U3") (pin "15") (pinfunction "VS_15") (pintype "power_in"))
      (node (ref "U5") (pin "15") (pinfunction "VS_15") (pintype "power_in"))
      (node (ref "U6") (pin "15") (pinfunction "VS_15") (pintype "power_in"))
    )
    (net (code "49") (name "PWR_GND") (class "Default")
      (node (ref "C14") (pin "1") (pinfunction "1_1") (pintype "passive"))
      (node (ref "C16") (pin "2") (pinfunction "2_2") (pintype "passive"))
      (node (ref "C21") (pin "1") (pinfunction "1_1") (pintype "passive"))
      (node (ref "C22") (pin "2") (pinfunction "2_2") (pintype "passive"))
      (node (ref "C4") (pin "1") (pinfunction "1_1") (pintype "passive"))
      (node (ref "C7") (pin "1") (pinfunction "1_1") (pintype "passive"))
      (node (ref "C8") (pin "2") (pinfunction "2_2") (pintype "passive"))
      (node (ref "C9") (pin "2") (pinfunction "2_2") (pintype "passive"))
      (node (ref "D0") (pin "1") (pinfunction "1_1") (pintype "passive"))
      (node (ref "D014") (pin "A") (pinfunction "A_A") (pintype "passive"))
      (node (ref "D016") (pin "A") (pinfunction "A_A") (pintype "passive"))
      (node (ref "D018") (pin "A") (pinfunction "A_A") (pintype "passive"))
      (node (ref "D019") (pin "A") (pinfunction "A_A") (pintype "passive"))
      (node (ref "D020") (pin "A") (pinfunction "A_A") (pintype "passive"))
      (node (ref "D021") (pin "A") (pinfunction "A_A") (pintype "passive"))
      (node (ref "D022") (pin "A") (pinfunction "A_A") (pintype "passive"))
      (node (ref "D023") (pin "A") (pinfunction "A_A") (pintype "passive"))
      (node (ref "J1") (pin "1") (pinfunction "1_1") (pintype "passive"))
      (node (ref "J1") (pin "4") (pinfunction "4_4") (pintype "passive"))
      (node (ref "J1") (pin "5") (pinfunction "5_5") (pintype "passive"))
      (node (ref "J1") (pin "A1") (pinfunction "1_A1") (pintype "passive"))
      (node (ref "J1") (pin "A4") (pinfunction "4_A4") (pintype "passive"))
      (node (ref "J1") (pin "A5") (pinfunction "5_A5") (pintype "passive"))
      (node (ref "J13") (pin "3") (pinfunction "3_3") (pintype "passive"))
      (node (ref "J13") (pin "5") (pinfunction "5_5") (pintype "passive"))
      (node (ref "J13") (pin "A3") (pinfunction "3_A3") (pintype "passive"))
      (node (ref "J13") (pin "A5") (pinfunction "5_A5") (pintype "passive"))
      (node (ref "J15") (pin "3") (pinfunction "3_3") (pintype "passive"))
      (node (ref "J15") (pin "4") (pinfunction "4_4") (pintype "passive"))
      (node (ref "J15") (pin "7") (pinfunction "7_7") (pintype "passive"))
      (node (ref "J15") (pin "8") (pinfunction "8_8") (pintype "passive"))
      (node (ref "J15") (pin "A3") (pinfunction "3_A3") (pintype "passive"))
      (node (ref "J15") (pin "A4") (pinfunction "4_A4") (pintype "passive"))
      (node (ref "J15") (pin "A7") (pinfunction "7_A7") (pintype "passive"))
      (node (ref "J15") (pin "A8") (pinfunction "8_A8") (pintype "passive"))
      (node (ref "J9") (pin "1") (pinfunction "1_1") (pintype "passive"))
      (node (ref "J9") (pin "3") (pinfunction "3_3") (pintype "passive"))
      (node (ref "J9") (pin "5") (pinfunction "5_5") (pintype "passive"))
      (node (ref "RX1") (pin "1") (pinfunction "1_1") (pintype "passive"))
      (node (ref "RX2") (pin "2") (pinfunction "2_2") (pintype "passive"))
      (node (ref "RX3") (pin "1") (pinfunction "1_1") (pintype "passive"))
      (node (ref "RX4") (pin "2") (pinfunction "2_2") (pintype "passive"))
      (node (ref "RX5") (pin "2") (pinfunction "2_2") (pintype "passive"))
      (node (ref "RX6") (pin "2") (pinfunction "2_2") (pintype "passive"))
      (node (ref "RX7") (pin "1") (pinfunction "1_1") (pintype "passive"))
      (node (ref "RX8") (pin "1") (pinfunction "1_1") (pintype "passive"))
    )
    (net (code "50") (name "Q1") (class "Default")
      (node (ref "C7") (pin "2") (pinfunction "2_2") (pintype "passive"))
      (node (ref "D014") (pin "C") (pinfunction "C_C") (pintype "passive"))
      (node (ref "D1") (pin "2") (pinfunction "+_2") (pintype "passive"))
      (node (ref "J13") (pin "2") (pinfunction "2_2") (pintype "passive"))
      (node (ref "J13") (pin "A2") (pinfunction "2_A2") (pintype "passive"))
      (node (ref "U2") (pin "10") (pinfunction "OUT1C_10") (pintype "output"))
      (node (ref "U2") (pin "8") (pinfunction "OUT1A_8") (pintype "output"))
      (node (ref "U2") (pin "9") (pinfunction "OUT1B_9") (pintype "output"))
    )
    (net (code "51") (name "Q1C") (class "Default")
      (node (ref "ESP32-J3") (pin "18") (pinfunction "18_18") (pintype "passive"))
      (node (ref "R13") (pin "1") (pinfunction "1_1") (pintype "passive"))
      (node (ref "R33") (pin "2") (pinfunction "2_2") (pintype "passive"))
    )
    (net (code "52") (name "Q2") (class "Default")
      (node (ref "C8") (pin "1") (pinfunction "1_1") (pintype "passive"))
      (node (ref "D019") (pin "C") (pinfunction "C_C") (pintype "passive"))
      (node (ref "D2") (pin "2") (pinfunction "+_2") (pintype "passive"))
      (node (ref "J13") (pin "1") (pinfunction "1_1") (pintype "passive"))
      (node (ref "J13") (pin "A1") (pinfunction "1_A1") (pintype "passive"))
      (node (ref "U2") (pin "12") (pinfunction "OUT0A_12") (pintype "output"))
      (node (ref "U2") (pin "13") (pinfunction "OUT0B_13") (pintype "output"))
      (node (ref "U2") (pin "14") (pinfunction "OUT0C_14") (pintype "output"))
    )
    (net (code "53") (name "Q2C") (class "Default")
      (node (ref "ESP32-J3") (pin "17") (pinfunction "17_17") (pintype "passive"))
      (node (ref "R15") (pin "2") (pinfunction "2_2") (pintype "passive"))
      (node (ref "R18") (pin "1") (pinfunction "1_1") (pintype "passive"))
    )
    (net (code "54") (name "Q3") (class "Default")
      (node (ref "C4") (pin "2") (pinfunction "2_2") (pintype "passive"))
      (node (ref "D016") (pin "C") (pinfunction "C_C") (pintype "passive"))
      (node (ref "D3") (pin "2") (pinfunction "+_2") (pintype "passive"))
      (node (ref "J15") (pin "6") (pinfunction "6_6") (pintype "passive"))
      (node (ref "J15") (pin "A6") (pinfunction "6_A6") (pintype "passive"))
      (node (ref "U3") (pin "10") (pinfunction "OUT1C_10") (pintype "output"))
      (node (ref "U3") (pin "8") (pinfunction "OUT1A_8") (pintype "output"))
      (node (ref "U3") (pin "9") (pinfunction "OUT1B_9") (pintype "output"))
    )
    (net (code "55") (name "Q3C") (class "Default")
      (node (ref "ESP32-J3") (pin "9") (pinfunction "9_9") (pintype "passive"))
      (node (ref "R14") (pin "2") (pinfunction "2_2") (pintype "passive"))
      (node (ref "R4") (pin "1") (pinfunction "1_1") (pintype "passive"))
    )
    (net (code "56") (name "Q4") (class "Default")
      (node (ref "C9") (pin "1") (pinfunction "1_1") (pintype "passive"))
      (node (ref "D018") (pin "C") (pinfunction "C_C") (pintype "passive"))
      (node (ref "D4") (pin "2") (pinfunction "+_2") (pintype "passive"))
      (node (ref "J15") (pin "5") (pinfunction "5_5") (pintype "passive"))
      (node (ref "J15") (pin "A5") (pinfunction "5_A5") (pintype "passive"))
      (node (ref "U3") (pin "12") (pinfunction "OUT0A_12") (pintype "output"))
      (node (ref "U3") (pin "13") (pinfunction "OUT0B_13") (pintype "output"))
      (node (ref "U3") (pin "14") (pinfunction "OUT0C_14") (pintype "output"))
    )
    (net (code "57") (name "Q4C") (class "Default")
      (node (ref "ESP32-J3") (pin "8") (pinfunction "8_8") (pintype "passive"))
      (node (ref "R16") (pin "2") (pinfunction "2_2") (pintype "passive"))
      (node (ref "R2") (pin "1") (pinfunction "1_1") (pintype "passive"))
    )
    (net (code "58") (name "Q5") (class "Default")
      (node (ref "C14") (pin "2") (pinfunction "2_2") (pintype "passive"))
      (node (ref "D020") (pin "C") (pinfunction "C_C") (pintype "passive"))
      (node (ref "D8") (pin "2") (pinfunction "+_2") (pintype "passive"))
      (node (ref "J15") (pin "2") (pinfunction "2_2") (pintype "passive"))
      (node (ref "J15") (pin "A2") (pinfunction "2_A2") (pintype "passive"))
      (node (ref "U5") (pin "10") (pinfunction "OUT1C_10") (pintype "output"))
      (node (ref "U5") (pin "8") (pinfunction "OUT1A_8") (pintype "output"))
      (node (ref "U5") (pin "9") (pinfunction "OUT1B_9") (pintype "output"))
    )
    (net (code "59") (name "Q5C") (class "Default")
      (node (ref "ESP32-J3") (pin "7") (pinfunction "7_7") (pintype "passive"))
      (node (ref "R17") (pin "2") (pinfunction "2_2") (pintype "passive"))
      (node (ref "R6") (pin "1") (pinfunction "1_1") (pintype "passive"))
    )
    (net (code "60") (name "Q6") (class "Default")
      (node (ref "C16") (pin "1") (pinfunction "1_1") (pintype "passive"))
      (node (ref "D021") (pin "C") (pinfunction "C_C") (pintype "passive"))
      (node (ref "D7") (pin "2") (pinfunction "+_2") (pintype "passive"))
      (node (ref "J15") (pin "1") (pinfunction "1_1") (pintype "passive"))
      (node (ref "J15") (pin "A1") (pinfunction "1_A1") (pintype "passive"))
      (node (ref "U5") (pin "12") (pinfunction "OUT0A_12") (pintype "output"))
      (node (ref "U5") (pin "13") (pinfunction "OUT0B_13") (pintype "output"))
      (node (ref "U5") (pin "14") (pinfunction "OUT0C_14") (pintype "output"))
    )
    (net (code "61") (name "Q6C") (class "Default")
      (node (ref "ESP32-J3") (pin "6") (pinfunction "6_6") (pintype "passive"))
      (node (ref "R19") (pin "2") (pinfunction "2_2") (pintype "passive"))
      (node (ref "R5") (pin "1") (pinfunction "1_1") (pintype "passive"))
    )
    (net (code "62") (name "Q7") (class "Default")
      (node (ref "C21") (pin "2") (pinfunction "2_2") (pintype "passive"))
      (node (ref "D022") (pin "C") (pinfunction "C_C") (pintype "passive"))
      (node (ref "D10") (pin "2") (pinfunction "+_2") (pintype "passive"))
      (node (ref "J1") (pin "3") (pinfunction "3_3") (pintype "passive"))
      (node (ref "J1") (pin "A3") (pinfunction "3_A3") (pintype "passive"))
      (node (ref "U6") (pin "10") (pinfunction "OUT1C_10") (pintype "output"))
      (node (ref "U6") (pin "8") (pinfunction "OUT1A_8") (pintype "output"))
      (node (ref "U6") (pin "9") (pinfunction "OUT1B_9") (pintype "output"))
    )
    (net (code "63") (name "Q7C") (class "Default")
      (node (ref "ESP32-J3") (pin "4") (pinfunction "4_4") (pintype "passive"))
      (node (ref "R11") (pin "1") (pinfunction "1_1") (pintype "passive"))
      (node (ref "R20") (pin "2") (pinfunction "2_2") (pintype "passive"))
    )
    (net (code "64") (name "Q8") (class "Default")
      (node (ref "C22") (pin "1") (pinfunction "1_1") (pintype "passive"))
      (node (ref "D023") (pin "C") (pinfunction "C_C") (pintype "passive"))
      (node (ref "D9") (pin "2") (pinfunction "+_2") (pintype "passive"))
      (node (ref "J1") (pin "2") (pinfunction "2_2") (pintype "passive"))
      (node (ref "J1") (pin "A2") (pinfunction "2_A2") (pintype "passive"))
      (node (ref "U6") (pin "12") (pinfunction "OUT0A_12") (pintype "output"))
      (node (ref "U6") (pin "13") (pinfunction "OUT0B_13") (pintype "output"))
      (node (ref "U6") (pin "14") (pinfunction "OUT0C_14") (pintype "output"))
    )
    (net (code "65") (name "Q8C") (class "Default")
      (node (ref "ESP32-J3") (pin "5") (pinfunction "5_5") (pintype "passive"))
      (node (ref "R34") (pin "2") (pinfunction "2_2") (pintype "passive"))
      (node (ref "R9") (pin "1") (pinfunction "1_1") (pintype "passive"))
    )
    (net (code "66") (name "RESET") (class "Default")
      (node (ref "ESP32-J1") (pin "3") (pinfunction "3_3") (pintype "passive"))
      (node (ref "RESET") (pin "3") (pinfunction "3_3") (pintype "passive"))
    )
    (net (code "67") (name "U2IS") (class "Default")
      (node (ref "R35") (pin "2") (pinfunction "2_2") (pintype "passive"))
      (node (ref "U2") (pin "4") (pinfunction "IS_4") (pintype "output"))
    )
    (net (code "68") (name "U3IS") (class "Default")
      (node (ref "R36") (pin "2") (pinfunction "2_2") (pintype "passive"))
      (node (ref "U3") (pin "4") (pinfunction "IS_4") (pintype "output"))
    )
    (net (code "69") (name "U5IS") (class "Default")
      (node (ref "R37") (pin "2") (pinfunction "2_2") (pintype "passive"))
      (node (ref "U5") (pin "4") (pinfunction "IS_4") (pintype "output"))
    )
    (net (code "70") (name "U6IS") (class "Default")
      (node (ref "R38") (pin "2") (pinfunction "2_2") (pintype "passive"))
      (node (ref "U6") (pin "4") (pinfunction "IS_4") (pintype "output"))
    )
    (net (code "71") (name "unconnected-(ESP32-J1-Pad8)") (class "Default")
      (node (ref "ESP32-J1") (pin "8") (pinfunction "8_8") (pintype "passive"))
    )
    (net (code "72") (name "unconnected-(ESP32-J1-Pad9)") (class "Default")
      (node (ref "ESP32-J1") (pin "9") (pinfunction "9_9") (pintype "passive"))
    )
    (net (code "73") (name "unconnected-(ESP32-J1-Pad12)") (class "Default")
      (node (ref "ESP32-J1") (pin "12") (pinfunction "12_12") (pintype "passive"))
    )
    (net (code "74") (name "unconnected-(ESP32-J1-Pad14)") (class "Default")
      (node (ref "ESP32-J1") (pin "14") (pinfunction "14_14") (pintype "passive"))
    )
    (net (code "75") (name "unconnected-(ESP32-J1-Pad16)") (class "Default")
      (node (ref "ESP32-J1") (pin "16") (pinfunction "16_16") (pintype "passive"))
    )
    (net (code "76") (name "unconnected-(ESP32-J1-Pad17)") (class "Default")
      (node (ref "ESP32-J1") (pin "17") (pinfunction "17_17") (pintype "passive"))
    )
    (net (code "77") (name "unconnected-(ESP32-J1-Pad20)") (class "Default")
      (node (ref "ESP32-J1") (pin "20") (pinfunction "20_20") (pintype "passive"))
    )
    (net (code "78") (name "unconnected-(ESP32-J3-Pad2)") (class "Default")
      (node (ref "ESP32-J3") (pin "2") (pinfunction "2_2") (pintype "passive"))
    )
    (net (code "79") (name "unconnected-(ESP32-J3-Pad3)") (class "Default")
      (node (ref "ESP32-J3") (pin "3") (pinfunction "3_3") (pintype "passive"))
    )
    (net (code "80") (name "unconnected-(ESP32-J3-Pad10)") (class "Default")
      (node (ref "ESP32-J3") (pin "10") (pinfunction "10_10") (pintype "passive"))
    )
    (net (code "81") (name "unconnected-(ESP32-J3-Pad11)") (class "Default")
      (node (ref "ESP32-J3") (pin "11") (pinfunction "11_11") (pintype "passive"))
    )
    (net (code "82") (name "unconnected-(ESP32-J3-Pad12)") (class "Default")
      (node (ref "ESP32-J3") (pin "12") (pinfunction "12_12") (pintype "passive"))
    )
    (net (code "83") (name "unconnected-(ESP32-J3-Pad13)") (class "Default")
      (node (ref "ESP32-J3") (pin "13") (pinfunction "13_13") (pintype "passive"))
    )
    (net (code "84") (name "unconnected-(ESP32-J3-Pad15)") (class "Default")
      (node (ref "ESP32-J3") (pin "15") (pinfunction "15_15") (pintype "passive"))
    )
    (net (code "85") (name "unconnected-(ESP32-J3-Pad16)") (class "Default")
      (node (ref "ESP32-J3") (pin "16") (pinfunction "16_16") (pintype "passive"))
    )
    (net (code "86") (name "unconnected-(ESP32-J3-Pad19)") (class "Default")
      (node (ref "ESP32-J3") (pin "19") (pinfunction "19_19") (pintype "passive"))
    )
    (net (code "87") (name "unconnected-(ESP32-J3-Pad20)") (class "Default")
      (node (ref "ESP32-J3") (pin "20") (pinfunction "20_20") (pintype "passive"))
    )
    (net (code "88") (name "unconnected-(U2-DEN-Pad3)") (class "Default")
      (node (ref "U2") (pin "3") (pinfunction "DEN_3") (pintype "input"))
    )
    (net (code "89") (name "unconnected-(U2-DSEL-Pad5)") (class "Default")
      (node (ref "U2") (pin "5") (pinfunction "DSEL_5") (pintype "input"))
    )
    (net (code "90") (name "unconnected-(U2-NC1-Pad7)") (class "Default")
      (node (ref "U2") (pin "7") (pinfunction "NC1_7") (pintype "passive"))
    )
    (net (code "91") (name "unconnected-(U2-NC2-Pad11)") (class "Default")
      (node (ref "U2") (pin "11") (pinfunction "NC2_11") (pintype "passive"))
    )
    (net (code "92") (name "unconnected-(U3-DEN-Pad3)") (class "Default")
      (node (ref "U3") (pin "3") (pinfunction "DEN_3") (pintype "input"))
    )
    (net (code "93") (name "unconnected-(U3-DSEL-Pad5)") (class "Default")
      (node (ref "U3") (pin "5") (pinfunction "DSEL_5") (pintype "input"))
    )
    (net (code "94") (name "unconnected-(U3-NC1-Pad7)") (class "Default")
      (node (ref "U3") (pin "7") (pinfunction "NC1_7") (pintype "passive"))
    )
    (net (code "95") (name "unconnected-(U3-NC2-Pad11)") (class "Default")
      (node (ref "U3") (pin "11") (pinfunction "NC2_11") (pintype "passive"))
    )
    (net (code "96") (name "unconnected-(U5-DEN-Pad3)") (class "Default")
      (node (ref "U5") (pin "3") (pinfunction "DEN_3") (pintype "input"))
    )
    (net (code "97") (name "unconnected-(U5-DSEL-Pad5)") (class "Default")
      (node (ref "U5") (pin "5") (pinfunction "DSEL_5") (pintype "input"))
    )
    (net (code "98") (name "unconnected-(U5-NC1-Pad7)") (class "Default")
      (node (ref "U5") (pin "7") (pinfunction "NC1_7") (pintype "passive"))
    )
    (net (code "99") (name "unconnected-(U5-NC2-Pad11)") (class "Default")
      (node (ref "U5") (pin "11") (pinfunction "NC2_11") (pintype "passive"))
    )
    (net (code "100") (name "unconnected-(U6-DEN-Pad3)") (class "Default")
      (node (ref "U6") (pin "3") (pinfunction "DEN_3") (pintype "input"))
    )
    (net (code "101") (name "unconnected-(U6-DSEL-Pad5)") (class "Default")
      (node (ref "U6") (pin "5") (pinfunction "DSEL_5") (pintype "input"))
    )
    (net (code "102") (name "unconnected-(U6-NC1-Pad7)") (class "Default")
      (node (ref "U6") (pin "7") (pinfunction "NC1_7") (pintype "passive"))
    )
    (net (code "103") (name "unconnected-(U6-NC2-Pad11)") (class "Default")
      (node (ref "U6") (pin "11") (pinfunction "NC2_11") (pintype "passive"))
    )
  )
)
